# MainBoard.net
KiCad netlist of a schematic drawn in Altium Designer
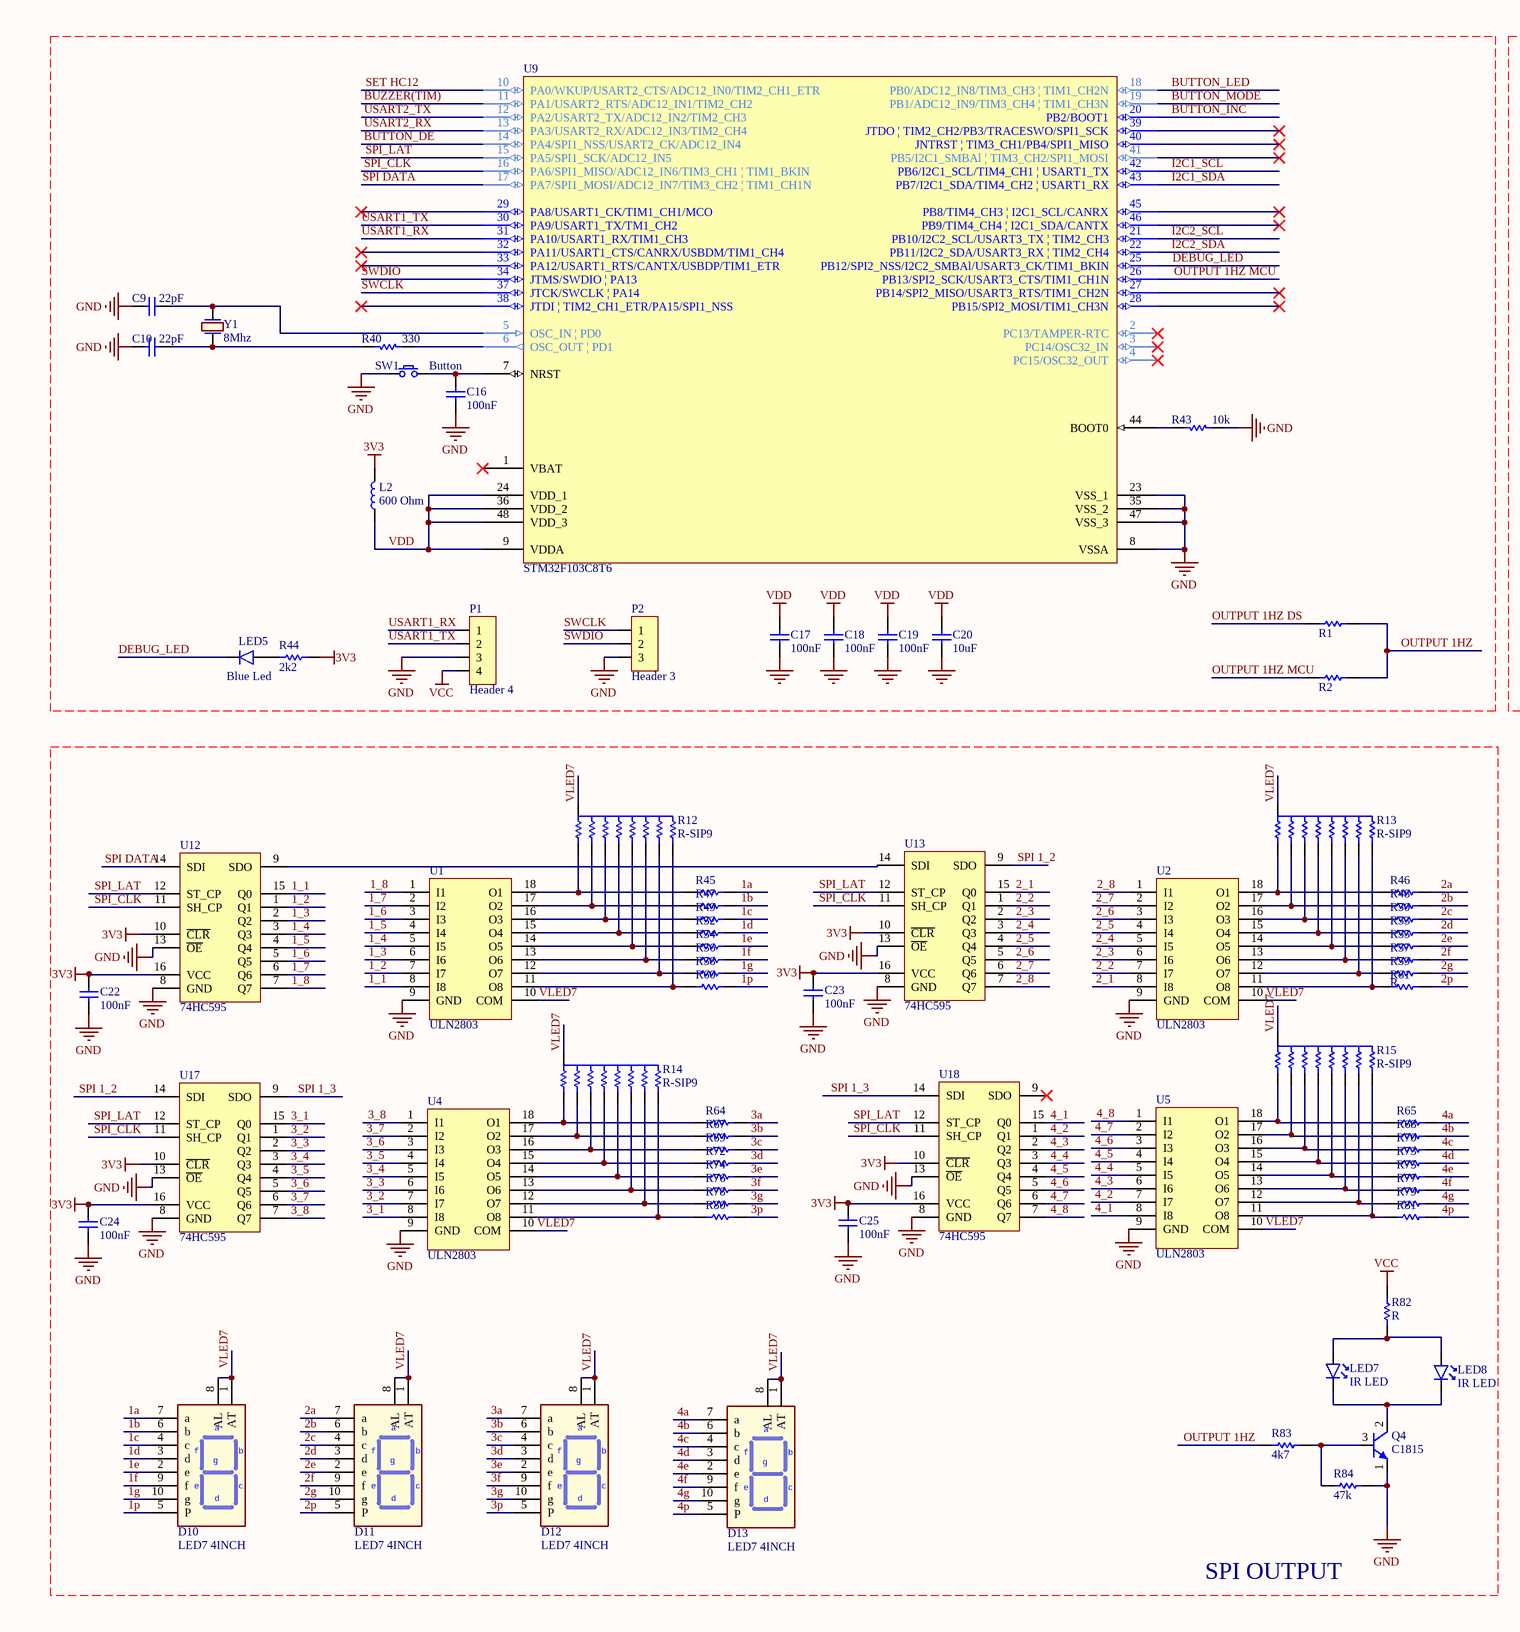
[diagram p0: MainBoard.SchDoc, left]
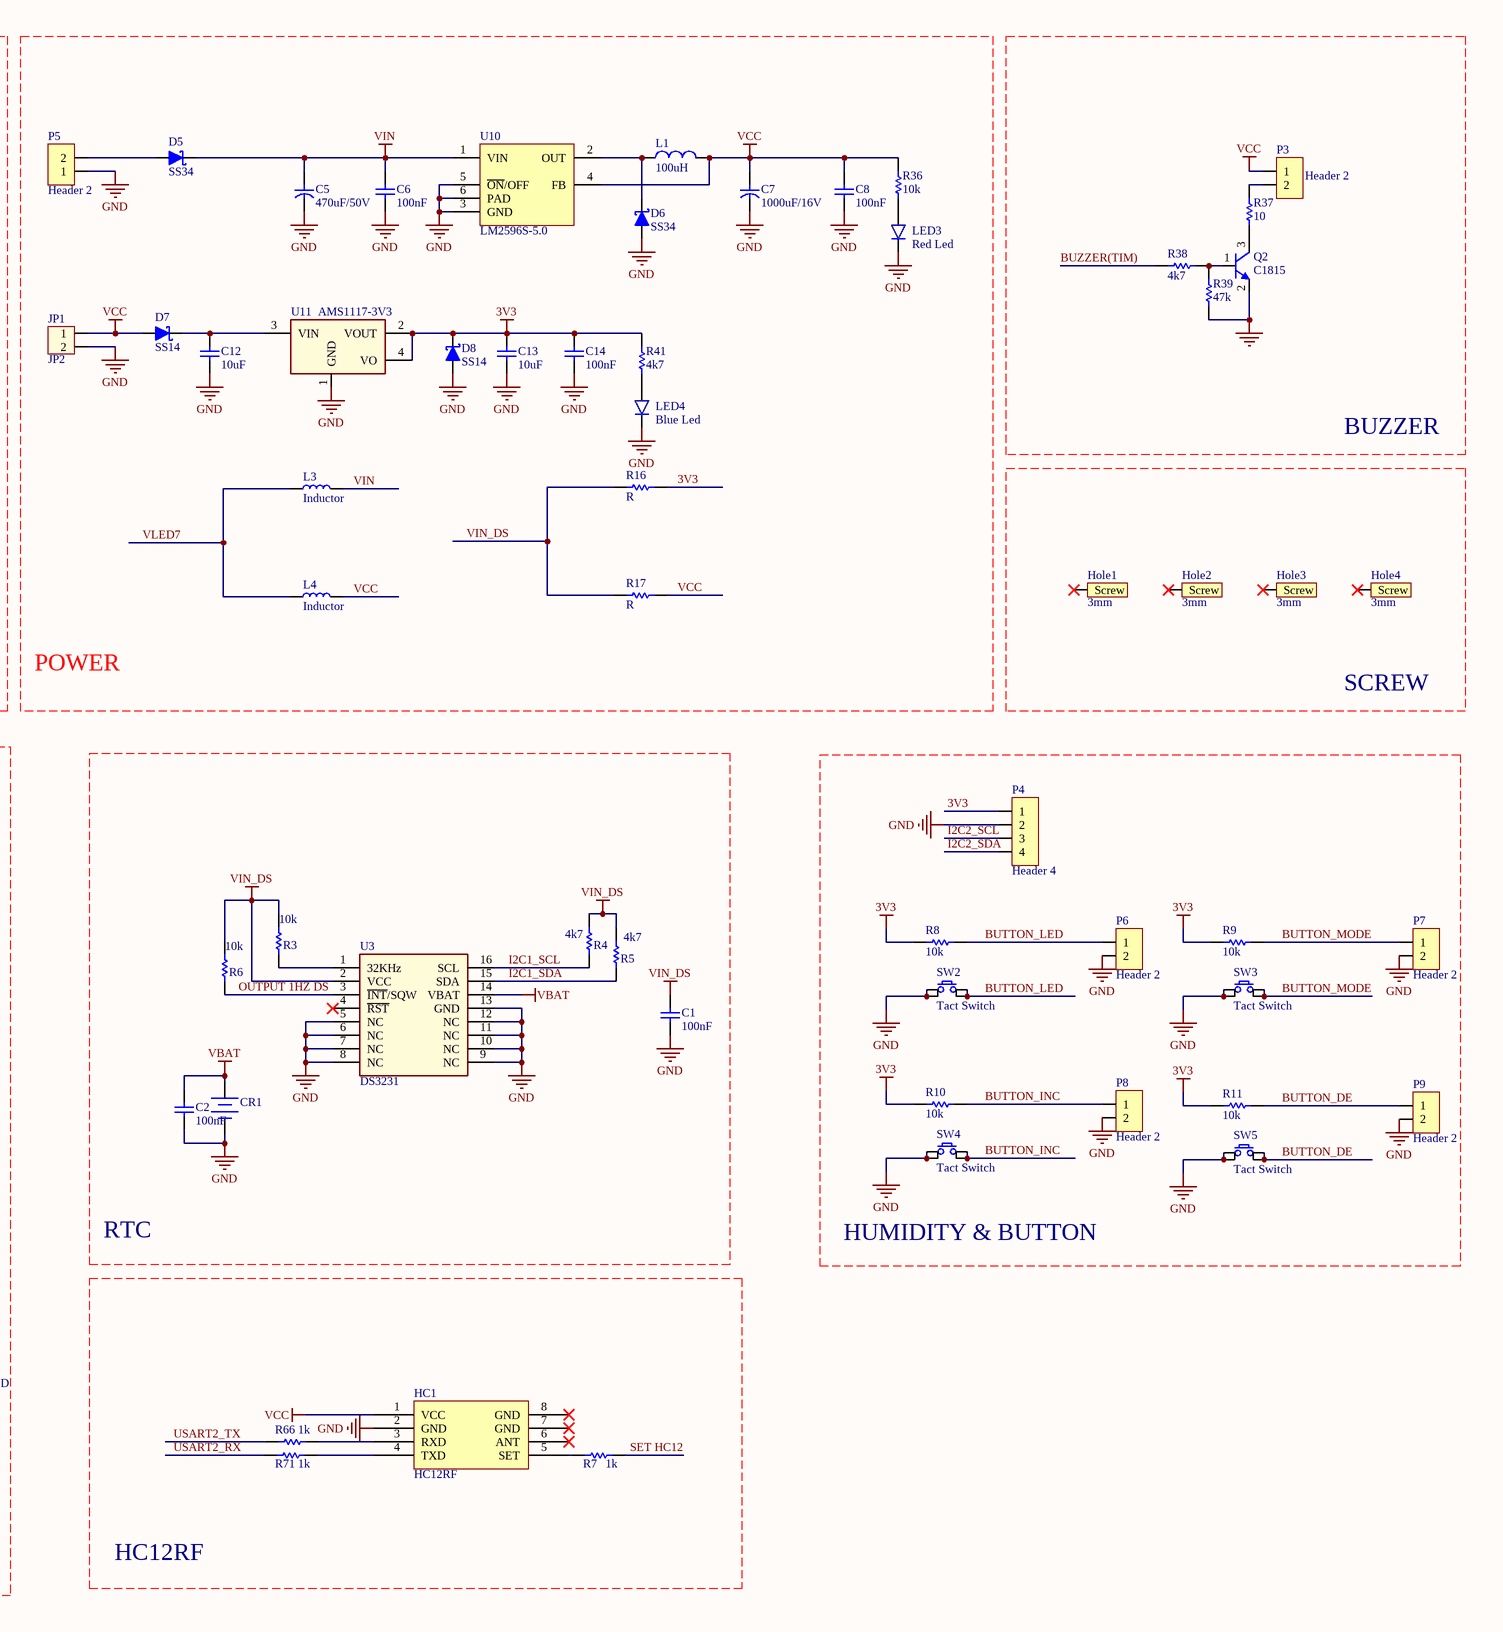
[diagram p1: MainBoard.SchDoc, right]

(export (version "E")
  (design (tool "Eeschema 10.0.6"))
  (components
    (comp (ref "C1")
      (value "100nF")
      (footprint "C 0805 (2012)")
      (description "Capacitor non-pol")
      (libsource (lib "BKIT4U_LIB") (part "Capacitor NP"))
    )
    (comp (ref "C2")
      (value "100nF")
      (footprint "C 0805 (2012)")
      (description "Capacitor non-pol")
      (libsource (lib "BKIT4U_LIB") (part "Capacitor NP"))
    )
    (comp (ref "C5")
      (value "470uF/50V")
      (footprint "CR/D.10.0x16.0/P.5.0")
      (description "Capacitor pol")
      (libsource (lib "BKIT4U_LIB") (part "Capacitor"))
    )
    (comp (ref "C6")
      (value "100nF")
      (footprint "C 0805 (2012)")
      (description "Capacitor non-pol")
      (libsource (lib "BKIT4U_LIB") (part "Capacitor NP"))
    )
    (comp (ref "C7")
      (value "1000uF/16V")
      (footprint "CR/D.10.0x12.5/P.5.0")
      (description "Capacitor pol")
      (libsource (lib "BKIT4U_LIB") (part "Capacitor"))
    )
    (comp (ref "C8")
      (value "100nF")
      (footprint "C 0805 (2012)")
      (description "Capacitor non-pol")
      (libsource (lib "BKIT4U_LIB") (part "Capacitor NP"))
    )
    (comp (ref "C9")
      (value "22pF")
      (footprint "C 0805 (2012)")
      (description "Capacitor non-pol")
      (libsource (lib "BKIT4U_LIB") (part "Capacitor NP"))
    )
    (comp (ref "C10")
      (value "22pF")
      (footprint "C 0805 (2012)")
      (description "Capacitor non-pol")
      (libsource (lib "BKIT4U_LIB") (part "Capacitor NP"))
    )
    (comp (ref "C12")
      (value "10uF")
      (footprint "C 0805 (2012)")
      (description "Capacitor non-pol")
      (libsource (lib "BKIT4U_LIB") (part "Capacitor NP"))
    )
    (comp (ref "C13")
      (value "10uF")
      (footprint "C 0805 (2012)")
      (description "Capacitor non-pol")
      (libsource (lib "BKIT4U_LIB") (part "Capacitor NP"))
    )
    (comp (ref "C14")
      (value "100nF")
      (footprint "C 0805 (2012)")
      (description "Capacitor non-pol")
      (libsource (lib "BKIT4U_LIB") (part "Capacitor NP"))
    )
    (comp (ref "C16")
      (value "100nF")
      (footprint "C 0805 (2012)")
      (description "Capacitor non-pol")
      (libsource (lib "BKIT4U_LIB") (part "Capacitor NP"))
    )
    (comp (ref "C17")
      (value "100nF")
      (footprint "C 0805 (2012)")
      (description "Capacitor non-pol")
      (libsource (lib "BKIT4U_LIB") (part "Capacitor NP"))
    )
    (comp (ref "C18")
      (value "100nF")
      (footprint "C 0805 (2012)")
      (description "Capacitor non-pol")
      (libsource (lib "BKIT4U_LIB") (part "Capacitor NP"))
    )
    (comp (ref "C19")
      (value "100nF")
      (footprint "C 0805 (2012)")
      (description "Capacitor non-pol")
      (libsource (lib "BKIT4U_LIB") (part "Capacitor NP"))
    )
    (comp (ref "C20")
      (value "10uF")
      (footprint "C 0805 (2012)")
      (description "Capacitor non-pol")
      (libsource (lib "BKIT4U_LIB") (part "Capacitor NP"))
    )
    (comp (ref "C22")
      (value "100nF")
      (footprint "C 0805 (2012)")
      (description "Capacitor non-pol")
      (libsource (lib "BKIT4U_LIB") (part "Capacitor NP"))
    )
    (comp (ref "C23")
      (value "100nF")
      (footprint "C 0805 (2012)")
      (description "Capacitor non-pol")
      (libsource (lib "BKIT4U_LIB") (part "Capacitor NP"))
    )
    (comp (ref "C24")
      (value "100nF")
      (footprint "C 0805 (2012)")
      (description "Capacitor non-pol")
      (libsource (lib "BKIT4U_LIB") (part "Capacitor NP"))
    )
    (comp (ref "C25")
      (value "100nF")
      (footprint "C 0805 (2012)")
      (description "Capacitor non-pol")
      (libsource (lib "BKIT4U_LIB") (part "Capacitor NP"))
    )
    (comp (ref "CR1") (value "~") (footprint "CON CR1220") (libsource (lib "BKIT4U_LIB") (part "Battery")))
    (comp (ref "D5")
      (value "SS34")
      (footprint "DO-214AC (SMA)")
      (description "Schottky Diode")
      (fields (field (name "PUBLISHER") "Altium Limited"))
      (libsource (lib "BKIT4U_LIB") (part "Diode Schottky"))
    )
    (comp (ref "D6")
      (value "SS34")
      (footprint "DO-214AC (SMA)")
      (description "Schottky Diode")
      (fields (field (name "PUBLISHER") "Altium Limited"))
      (libsource (lib "BKIT4U_LIB") (part "Diode Schottky"))
    )
    (comp (ref "D7")
      (value "SS14")
      (footprint "DO-214AC (SMA)")
      (description "Schottky Diode")
      (fields (field (name "PUBLISHER") "Altium Limited"))
      (libsource (lib "BKIT4U_LIB") (part "Diode Schottky"))
    )
    (comp (ref "D8")
      (value "SS14")
      (footprint "DO-214AC (SMA)")
      (description "Schottky Diode")
      (fields (field (name "PUBLISHER") "Altium Limited"))
      (libsource (lib "BKIT4U_LIB") (part "Diode Schottky"))
    )
    (comp (ref "D10")
      (value "LED7 4INCH")
      (footprint "LED7 CA 4INCH")
      (libsource (lib "BKIT4U_LIB") (part "LED7 4INCH"))
    )
    (comp (ref "D11")
      (value "LED7 4INCH")
      (footprint "LED7 CA 4INCH")
      (libsource (lib "BKIT4U_LIB") (part "LED7 4INCH"))
    )
    (comp (ref "D12")
      (value "LED7 4INCH")
      (footprint "LED7 CA 4INCH")
      (libsource (lib "BKIT4U_LIB") (part "LED7 4INCH"))
    )
    (comp (ref "D13")
      (value "LED7 4INCH")
      (footprint "LED7 CA 4INCH")
      (libsource (lib "BKIT4U_LIB") (part "LED7 4INCH"))
    )
    (comp (ref "HC1") (value "HC12RF") (footprint "HC12RF") (libsource (lib "BKIT4U_LIB") (part "HC12RF")))
    (comp (ref "Hole1") (value "3mm") (footprint "SCREW/3M/7M") (libsource (lib "BKIT4U_LIB") (part "Screw")))
    (comp (ref "Hole2") (value "3mm") (footprint "SCREW/3M/7M") (libsource (lib "BKIT4U_LIB") (part "Screw")))
    (comp (ref "Hole3") (value "3mm") (footprint "SCREW/3M/7M") (libsource (lib "BKIT4U_LIB") (part "Screw")))
    (comp (ref "Hole4") (value "3mm") (footprint "SCREW/3M/7M") (libsource (lib "BKIT4U_LIB") (part "Screw")))
    (comp (ref "JP1")
      (value "JP2")
      (footprint "CON Header 2")
      (description "Connector 2")
      (libsource (lib "BKIT4U_LIB") (part "Con2"))
    )
    (comp (ref "L1")
      (value "100uH")
      (footprint "Inductor SMD 12x12x8")
      (description "Inductor")
      (libsource (lib "syhaunguyen") (part "L1"))
    )
    (comp (ref "L2")
      (value "600 Ohm")
      (footprint "Inductor SMD 0805 (2012)")
      (description "Inductor")
      (libsource (lib "BKIT4U_LIB") (part "Inductor"))
    )
    (comp (ref "L3")
      (value "Inductor")
      (footprint "Inductor SMD 7.5x7.0x5.0")
      (libsource (lib "BKIT4U_LIB") (part "Inductor"))
    )
    (comp (ref "L4")
      (value "Inductor")
      (footprint "Inductor SMD 7.5x7.0x5.0")
      (libsource (lib "BKIT4U_LIB") (part "Inductor"))
    )
    (comp (ref "LED3")
      (value "Red Led")
      (footprint "Led SMD 0805")
      (description "Typical LED")
      (libsource (lib "BKIT4U_LIB") (part "Led"))
    )
    (comp (ref "LED4")
      (value "Blue Led")
      (footprint "Led SMD 0805")
      (description "Typical LED")
      (libsource (lib "BKIT4U_LIB") (part "Led"))
    )
    (comp (ref "LED5")
      (value "Blue Led")
      (footprint "Led SMD 0805")
      (description "Typical LED")
      (libsource (lib "BKIT4U_LIB") (part "Led"))
    )
    (comp (ref "LED7")
      (value "IR LED")
      (footprint "LED 5MM")
      (description "IR Led")
      (fields (field (name "PUBLISHER") "Altium Limited"))
      (libsource (lib "BKIT4U_LIB") (part "IR Led"))
    )
    (comp (ref "LED8")
      (value "IR LED")
      (footprint "LED 5MM")
      (description "IR Led")
      (fields (field (name "PUBLISHER") "Altium Limited"))
      (libsource (lib "BKIT4U_LIB") (part "IR Led"))
    )
    (comp (ref "P1")
      (value "Header 4")
      (footprint "CON Header 4")
      (description "Header, 4-Pin")
      (libsource (lib "BKIT4U_LIB") (part "Header 4"))
    )
    (comp (ref "P2")
      (value "Header 3")
      (footprint "Header 3")
      (description "Header, 3-Pin")
      (libsource (lib "BKIT4U_LIB") (part "Header 3"))
    )
    (comp (ref "P3")
      (value "Header 2")
      (footprint "CON Header 2")
      (description "Header, 2-Pin")
      (fields (field (name "PUBLISHER") "Altium Limited"))
      (libsource (lib "BKIT4U_LIB") (part "Header 2"))
    )
    (comp (ref "P4")
      (value "Header 4")
      (footprint "Header 4")
      (description "Header, 4-Pin")
      (libsource (lib "BKIT4U_LIB") (part "Header 4"))
    )
    (comp (ref "P5")
      (value "Header 2")
      (footprint "HDR Domino 2")
      (description "Header, 2-Pin")
      (fields (field (name "PUBLISHER") "Altium Limited"))
      (libsource (lib "") (part "Header 2_1"))
    )
    (comp (ref "P6")
      (value "Header 2")
      (footprint "CON Header 2")
      (description "Header, 2-Pin")
      (fields (field (name "PUBLISHER") "Altium Limited"))
      (libsource (lib "BKIT4U_LIB") (part "Header 2"))
    )
    (comp (ref "P7")
      (value "Header 2")
      (footprint "CON Header 2")
      (description "Header, 2-Pin")
      (fields (field (name "PUBLISHER") "Altium Limited"))
      (libsource (lib "BKIT4U_LIB") (part "Header 2"))
    )
    (comp (ref "P8")
      (value "Header 2")
      (footprint "CON Header 2")
      (description "Header, 2-Pin")
      (fields (field (name "PUBLISHER") "Altium Limited"))
      (libsource (lib "BKIT4U_LIB") (part "Header 2"))
    )
    (comp (ref "P9")
      (value "Header 2")
      (footprint "CON Header 2")
      (description "Header, 2-Pin")
      (fields (field (name "PUBLISHER") "Altium Limited"))
      (libsource (lib "BKIT4U_LIB") (part "Header 2"))
    )
    (comp (ref "Q2")
      (value "C1815")
      (footprint "SOT-23")
      (description "NPN Bipolar Transistor")
      (libsource (lib "BKIT4U_LIB") (part "Transistor NPN"))
    )
    (comp (ref "Q4")
      (value "C1815")
      (footprint "SOT-23")
      (description "NPN Bipolar Transistor")
      (libsource (lib "BKIT4U_LIB") (part "Transistor NPN - C1815"))
    )
    (comp (ref "R1")
      (value "R")
      (footprint "R 0805 (2012)")
      (description "Resistor")
      (fields (field (name "PUBLISHER") "Altium Limited"))
      (libsource (lib "BKIT4U_LIB") (part "Resistor"))
    )
    (comp (ref "R2")
      (value "R")
      (footprint "R 0805 (2012)")
      (description "Resistor")
      (fields (field (name "PUBLISHER") "Altium Limited"))
      (libsource (lib "BKIT4U_LIB") (part "Resistor"))
    )
    (comp (ref "R3")
      (value "10k")
      (footprint "R 0805 (2012)")
      (description "Resistor")
      (fields (field (name "PUBLISHER") "Altium Limited"))
      (libsource (lib "BKIT4U_LIB") (part "Resistor"))
    )
    (comp (ref "R4")
      (value "4k7")
      (footprint "R 0805 (2012)")
      (description "Resistor")
      (fields (field (name "PUBLISHER") "Altium Limited"))
      (libsource (lib "BKIT4U_LIB") (part "Resistor"))
    )
    (comp (ref "R5")
      (value "4k7")
      (footprint "R 0805 (2012)")
      (description "Resistor")
      (fields (field (name "PUBLISHER") "Altium Limited"))
      (libsource (lib "BKIT4U_LIB") (part "Resistor"))
    )
    (comp (ref "R6")
      (value "10k")
      (footprint "R 0805 (2012)")
      (description "Resistor")
      (fields (field (name "PUBLISHER") "Altium Limited"))
      (libsource (lib "BKIT4U_LIB") (part "Resistor"))
    )
    (comp (ref "R7")
      (value "1k")
      (footprint "R 0805 (2012)")
      (description "Resistor")
      (fields (field (name "PUBLISHER") "Altium Limited"))
      (libsource (lib "BKIT4U_LIB") (part "Resistor"))
    )
    (comp (ref "R8")
      (value "10k")
      (footprint "R 0805 (2012)")
      (description "Resistor")
      (fields (field (name "PUBLISHER") "Altium Limited"))
      (libsource (lib "BKIT4U_LIB") (part "Resistor"))
    )
    (comp (ref "R9")
      (value "10k")
      (footprint "R 0805 (2012)")
      (description "Resistor")
      (fields (field (name "PUBLISHER") "Altium Limited"))
      (libsource (lib "BKIT4U_LIB") (part "Resistor"))
    )
    (comp (ref "R10")
      (value "10k")
      (footprint "R 0805 (2012)")
      (description "Resistor")
      (fields (field (name "PUBLISHER") "Altium Limited"))
      (libsource (lib "BKIT4U_LIB") (part "Resistor"))
    )
    (comp (ref "R11")
      (value "10k")
      (footprint "R 0805 (2012)")
      (description "Resistor")
      (fields (field (name "PUBLISHER") "Altium Limited"))
      (libsource (lib "BKIT4U_LIB") (part "Resistor"))
    )
    (comp (ref "R12")
      (value "R-SIP9")
      (footprint "R SIP9")
      (description "Resistor")
      (fields (field (name "PUBLISHER") "Altium Limited"))
      (libsource (lib "BKIT4U_LIB") (part "Resistor Sip9"))
    )
    (comp (ref "R13")
      (value "R-SIP9")
      (footprint "R SIP9")
      (description "Resistor")
      (fields (field (name "PUBLISHER") "Altium Limited"))
      (libsource (lib "BKIT4U_LIB") (part "Resistor Sip9"))
    )
    (comp (ref "R14")
      (value "R-SIP9")
      (footprint "R SIP9")
      (description "Resistor")
      (fields (field (name "PUBLISHER") "Altium Limited"))
      (libsource (lib "BKIT4U_LIB") (part "Resistor Sip9"))
    )
    (comp (ref "R15")
      (value "R-SIP9")
      (footprint "R SIP9")
      (description "Resistor")
      (fields (field (name "PUBLISHER") "Altium Limited"))
      (libsource (lib "BKIT4U_LIB") (part "Resistor Sip9"))
    )
    (comp (ref "R16")
      (value "R")
      (footprint "R 0805 (2012)")
      (description "Resistor")
      (fields (field (name "PUBLISHER") "Altium Limited"))
      (libsource (lib "BKIT4U_LIB") (part "Resistor"))
    )
    (comp (ref "R17")
      (value "R")
      (footprint "R 0805 (2012)")
      (description "Resistor")
      (fields (field (name "PUBLISHER") "Altium Limited"))
      (libsource (lib "BKIT4U_LIB") (part "Resistor"))
    )
    (comp (ref "R36")
      (value "10k")
      (footprint "R 0805 (2012)")
      (description "Resistor")
      (fields (field (name "PUBLISHER") "Altium Limited"))
      (libsource (lib "BKIT4U_LIB") (part "Resistor"))
    )
    (comp (ref "R37")
      (value "10")
      (footprint "R 0805 (2012)")
      (description "Resistor")
      (fields (field (name "PUBLISHER") "Altium Limited"))
      (libsource (lib "BKIT4U_LIB") (part "Resistor"))
    )
    (comp (ref "R38")
      (value "4k7")
      (footprint "R 0805 (2012)")
      (description "Resistor")
      (fields (field (name "PUBLISHER") "Altium Limited"))
      (libsource (lib "BKIT4U_LIB") (part "Resistor"))
    )
    (comp (ref "R39")
      (value "47k")
      (footprint "R 0805 (2012)")
      (description "Resistor")
      (fields (field (name "PUBLISHER") "Altium Limited"))
      (libsource (lib "BKIT4U_LIB") (part "Resistor"))
    )
    (comp (ref "R40")
      (value "330")
      (footprint "R 0805 (2012)")
      (description "Resistor")
      (fields (field (name "PUBLISHER") "Altium Limited"))
      (libsource (lib "BKIT4U_LIB") (part "Resistor"))
    )
    (comp (ref "R41")
      (value "4k7")
      (footprint "R 0805 (2012)")
      (description "Resistor")
      (fields (field (name "PUBLISHER") "Altium Limited"))
      (libsource (lib "BKIT4U_LIB") (part "Resistor"))
    )
    (comp (ref "R43")
      (value "10k")
      (footprint "R 0805 (2012)")
      (description "Resistor")
      (fields (field (name "PUBLISHER") "Altium Limited"))
      (libsource (lib "BKIT4U_LIB") (part "Resistor"))
    )
    (comp (ref "R44")
      (value "2k2")
      (footprint "R 0805 (2012)")
      (description "Resistor")
      (fields (field (name "PUBLISHER") "Altium Limited"))
      (libsource (lib "BKIT4U_LIB") (part "Resistor"))
    )
    (comp (ref "R45")
      (value "R")
      (footprint "R 0805 (2012)")
      (description "Resistor")
      (fields (field (name "PUBLISHER") "Altium Limited"))
      (libsource (lib "BKIT4U_LIB") (part "Resistor"))
    )
    (comp (ref "R46")
      (value "R")
      (footprint "R 0805 (2012)")
      (description "Resistor")
      (fields (field (name "PUBLISHER") "Altium Limited"))
      (libsource (lib "BKIT4U_LIB") (part "Resistor"))
    )
    (comp (ref "R47")
      (value "R")
      (footprint "R 0805 (2012)")
      (description "Resistor")
      (fields (field (name "PUBLISHER") "Altium Limited"))
      (libsource (lib "BKIT4U_LIB") (part "Resistor"))
    )
    (comp (ref "R48")
      (value "R")
      (footprint "R 0805 (2012)")
      (description "Resistor")
      (fields (field (name "PUBLISHER") "Altium Limited"))
      (libsource (lib "BKIT4U_LIB") (part "Resistor"))
    )
    (comp (ref "R49")
      (value "R")
      (footprint "R 0805 (2012)")
      (description "Resistor")
      (fields (field (name "PUBLISHER") "Altium Limited"))
      (libsource (lib "BKIT4U_LIB") (part "Resistor"))
    )
    (comp (ref "R50")
      (value "R")
      (footprint "R 0805 (2012)")
      (description "Resistor")
      (fields (field (name "PUBLISHER") "Altium Limited"))
      (libsource (lib "BKIT4U_LIB") (part "Resistor"))
    )
    (comp (ref "R52")
      (value "R")
      (footprint "R 0805 (2012)")
      (description "Resistor")
      (fields (field (name "PUBLISHER") "Altium Limited"))
      (libsource (lib "BKIT4U_LIB") (part "Resistor"))
    )
    (comp (ref "R53")
      (value "R")
      (footprint "R 0805 (2012)")
      (description "Resistor")
      (fields (field (name "PUBLISHER") "Altium Limited"))
      (libsource (lib "BKIT4U_LIB") (part "Resistor"))
    )
    (comp (ref "R54")
      (value "R")
      (footprint "R 0805 (2012)")
      (description "Resistor")
      (fields (field (name "PUBLISHER") "Altium Limited"))
      (libsource (lib "BKIT4U_LIB") (part "Resistor"))
    )
    (comp (ref "R55")
      (value "R")
      (footprint "R 0805 (2012)")
      (description "Resistor")
      (fields (field (name "PUBLISHER") "Altium Limited"))
      (libsource (lib "BKIT4U_LIB") (part "Resistor"))
    )
    (comp (ref "R56")
      (value "R")
      (footprint "R 0805 (2012)")
      (description "Resistor")
      (fields (field (name "PUBLISHER") "Altium Limited"))
      (libsource (lib "BKIT4U_LIB") (part "Resistor"))
    )
    (comp (ref "R57")
      (value "R")
      (footprint "R 0805 (2012)")
      (description "Resistor")
      (fields (field (name "PUBLISHER") "Altium Limited"))
      (libsource (lib "BKIT4U_LIB") (part "Resistor"))
    )
    (comp (ref "R58")
      (value "R")
      (footprint "R 0805 (2012)")
      (description "Resistor")
      (fields (field (name "PUBLISHER") "Altium Limited"))
      (libsource (lib "BKIT4U_LIB") (part "Resistor"))
    )
    (comp (ref "R59")
      (value "R")
      (footprint "R 0805 (2012)")
      (description "Resistor")
      (fields (field (name "PUBLISHER") "Altium Limited"))
      (libsource (lib "BKIT4U_LIB") (part "Resistor"))
    )
    (comp (ref "R60")
      (value "R")
      (footprint "R 0805 (2012)")
      (description "Resistor")
      (fields (field (name "PUBLISHER") "Altium Limited"))
      (libsource (lib "BKIT4U_LIB") (part "Resistor"))
    )
    (comp (ref "R61")
      (value "R")
      (footprint "R 0805 (2012)")
      (description "Resistor")
      (fields (field (name "PUBLISHER") "Altium Limited"))
      (libsource (lib "BKIT4U_LIB") (part "Resistor"))
    )
    (comp (ref "R64")
      (value "R")
      (footprint "R 0805 (2012)")
      (description "Resistor")
      (fields (field (name "PUBLISHER") "Altium Limited"))
      (libsource (lib "BKIT4U_LIB") (part "Resistor"))
    )
    (comp (ref "R65")
      (value "R")
      (footprint "R 0805 (2012)")
      (description "Resistor")
      (fields (field (name "PUBLISHER") "Altium Limited"))
      (libsource (lib "BKIT4U_LIB") (part "Resistor"))
    )
    (comp (ref "R66")
      (value "1k")
      (footprint "R 0805 (2012)")
      (description "Resistor")
      (fields (field (name "PUBLISHER") "Altium Limited"))
      (libsource (lib "BKIT4U_LIB") (part "Resistor"))
    )
    (comp (ref "R67")
      (value "R")
      (footprint "R 0805 (2012)")
      (description "Resistor")
      (fields (field (name "PUBLISHER") "Altium Limited"))
      (libsource (lib "BKIT4U_LIB") (part "Resistor"))
    )
    (comp (ref "R68")
      (value "R")
      (footprint "R 0805 (2012)")
      (description "Resistor")
      (fields (field (name "PUBLISHER") "Altium Limited"))
      (libsource (lib "BKIT4U_LIB") (part "Resistor"))
    )
    (comp (ref "R69")
      (value "R")
      (footprint "R 0805 (2012)")
      (description "Resistor")
      (fields (field (name "PUBLISHER") "Altium Limited"))
      (libsource (lib "BKIT4U_LIB") (part "Resistor"))
    )
    (comp (ref "R70")
      (value "R")
      (footprint "R 0805 (2012)")
      (description "Resistor")
      (fields (field (name "PUBLISHER") "Altium Limited"))
      (libsource (lib "BKIT4U_LIB") (part "Resistor"))
    )
    (comp (ref "R71")
      (value "1k")
      (footprint "R 0805 (2012)")
      (description "Resistor")
      (fields (field (name "PUBLISHER") "Altium Limited"))
      (libsource (lib "BKIT4U_LIB") (part "Resistor"))
    )
    (comp (ref "R72")
      (value "R")
      (footprint "R 0805 (2012)")
      (description "Resistor")
      (fields (field (name "PUBLISHER") "Altium Limited"))
      (libsource (lib "BKIT4U_LIB") (part "Resistor"))
    )
    (comp (ref "R73")
      (value "R")
      (footprint "R 0805 (2012)")
      (description "Resistor")
      (fields (field (name "PUBLISHER") "Altium Limited"))
      (libsource (lib "BKIT4U_LIB") (part "Resistor"))
    )
    (comp (ref "R74")
      (value "R")
      (footprint "R 0805 (2012)")
      (description "Resistor")
      (fields (field (name "PUBLISHER") "Altium Limited"))
      (libsource (lib "BKIT4U_LIB") (part "Resistor"))
    )
    (comp (ref "R75")
      (value "R")
      (footprint "R 0805 (2012)")
      (description "Resistor")
      (fields (field (name "PUBLISHER") "Altium Limited"))
      (libsource (lib "BKIT4U_LIB") (part "Resistor"))
    )
    (comp (ref "R76")
      (value "R")
      (footprint "R 0805 (2012)")
      (description "Resistor")
      (fields (field (name "PUBLISHER") "Altium Limited"))
      (libsource (lib "BKIT4U_LIB") (part "Resistor"))
    )
    (comp (ref "R77")
      (value "R")
      (footprint "R 0805 (2012)")
      (description "Resistor")
      (fields (field (name "PUBLISHER") "Altium Limited"))
      (libsource (lib "BKIT4U_LIB") (part "Resistor"))
    )
    (comp (ref "R78")
      (value "R")
      (footprint "R 0805 (2012)")
      (description "Resistor")
      (fields (field (name "PUBLISHER") "Altium Limited"))
      (libsource (lib "BKIT4U_LIB") (part "Resistor"))
    )
    (comp (ref "R79")
      (value "R")
      (footprint "R 0805 (2012)")
      (description "Resistor")
      (fields (field (name "PUBLISHER") "Altium Limited"))
      (libsource (lib "BKIT4U_LIB") (part "Resistor"))
    )
    (comp (ref "R80")
      (value "R")
      (footprint "R 0805 (2012)")
      (description "Resistor")
      (fields (field (name "PUBLISHER") "Altium Limited"))
      (libsource (lib "BKIT4U_LIB") (part "Resistor"))
    )
    (comp (ref "R81")
      (value "R")
      (footprint "R 0805 (2012)")
      (description "Resistor")
      (fields (field (name "PUBLISHER") "Altium Limited"))
      (libsource (lib "BKIT4U_LIB") (part "Resistor"))
    )
    (comp (ref "R82")
      (value "R")
      (footprint "R 0805 (2012)")
      (description "Resistor")
      (fields (field (name "PUBLISHER") "Altium Limited"))
      (libsource (lib "BKIT4U_LIB") (part "Resistor"))
    )
    (comp (ref "R83")
      (value "4k7")
      (footprint "R 0805 (2012)")
      (description "Resistor")
      (fields (field (name "PUBLISHER") "Altium Limited"))
      (libsource (lib "BKIT4U_LIB") (part "Resistor"))
    )
    (comp (ref "R84")
      (value "47k")
      (footprint "R 0805 (2012)")
      (description "Resistor")
      (fields (field (name "PUBLISHER") "Altium Limited"))
      (libsource (lib "BKIT4U_LIB") (part "Resistor"))
    )
    (comp (ref "SW1")
      (value "Button")
      (footprint "SW/2/SMD")
      (description "Tact switch 2 pin")
      (libsource (lib "BKIT4U_LIB") (part "SW SPST"))
    )
    (comp (ref "SW2")
      (value "Tact Switch")
      (footprint "SW/4/SMD/SMALL")
      (description "Tact switch 4 pin")
      (libsource (lib "BKIT4U_LIB") (part "SW SPST-4"))
    )
    (comp (ref "SW3")
      (value "Tact Switch")
      (footprint "SW/4/SMD/SMALL")
      (description "Tact switch 4 pin")
      (libsource (lib "BKIT4U_LIB") (part "SW SPST-4"))
    )
    (comp (ref "SW4")
      (value "Tact Switch")
      (footprint "SW/4/SMD/SMALL")
      (description "Tact switch 4 pin")
      (libsource (lib "BKIT4U_LIB") (part "SW SPST-4"))
    )
    (comp (ref "SW5")
      (value "Tact Switch")
      (footprint "SW/4/SMD/SMALL")
      (description "Tact switch 4 pin")
      (libsource (lib "BKIT4U_LIB") (part "SW SPST-4"))
    )
    (comp (ref "U1")
      (value "ULN2803")
      (footprint "SOIC-18")
      (description "High-voltage, high-current Darlington transistor arrays")
      (libsource (lib "BKIT4U_LIB") (part "ULN2803"))
    )
    (comp (ref "U2")
      (value "ULN2803")
      (footprint "SOIC-18")
      (description "High-voltage, high-current Darlington transistor arrays")
      (libsource (lib "BKIT4U_LIB") (part "ULN2803"))
    )
    (comp (ref "U3")
      (value "DS3231")
      (footprint "SOIC-16-WIDE")
      (libsource (lib "BKIT4U_LIB") (part "DS3231"))
    )
    (comp (ref "U4")
      (value "ULN2803")
      (footprint "SOIC-18")
      (description "High-voltage, high-current Darlington transistor arrays")
      (libsource (lib "BKIT4U_LIB") (part "ULN2803"))
    )
    (comp (ref "U5")
      (value "ULN2803")
      (footprint "SOIC-18")
      (description "High-voltage, high-current Darlington transistor arrays")
      (libsource (lib "BKIT4U_LIB") (part "ULN2803"))
    )
    (comp (ref "U9")
      (value "STM32F103C8T6")
      (footprint "LQFP48_N")
      (description "STM32 ARM-based 32-bit MCU with 64 Kbytes Flash, 48-pin LQFP, Industrial Temperature")
      (fields (field (name "PUBLISHER") "Altium Limited"))
      (libsource (lib "BKIT4U_LIB") (part "STM32F103C8T6"))
    )
    (comp (ref "U10")
      (value "LM2596S-5.0")
      (footprint "TO-263-5")
      (description "SIMPLE SWITCHER® 3A Step-Down Voltage Regulator")
      (libsource (lib "BKIT4U_LIB") (part "LM2576/96"))
    )
    (comp (ref "U11")
      (value "AMS1117-3V3")
      (footprint "SOT-223")
      (description "1A LDO Voltage Regulator, ADJ or fixed 1.5/1.8/2.5/2.85/3.3/5V")
      (libsource (lib "BKIT4U_LIB") (part "AMS1117"))
    )
    (comp (ref "U12")
      (value "74HC595")
      (footprint "SOIC-16")
      (description "8-bit serial-in, serial or parallel-out  shift register with output latches;  3-state")
      (libsource (lib "BKIT4U_LIB") (part "74HC595"))
    )
    (comp (ref "U13")
      (value "74HC595")
      (footprint "SOIC-16")
      (description "8-bit serial-in, serial or parallel-out  shift register with output latches;  3-state")
      (libsource (lib "BKIT4U_LIB") (part "74HC595"))
    )
    (comp (ref "U17")
      (value "74HC595")
      (footprint "SOIC-16")
      (description "8-bit serial-in, serial or parallel-out  shift register with output latches;  3-state")
      (libsource (lib "BKIT4U_LIB") (part "74HC595"))
    )
    (comp (ref "U18")
      (value "74HC595")
      (footprint "SOIC-16")
      (description "8-bit serial-in, serial or parallel-out  shift register with output latches;  3-state")
      (libsource (lib "BKIT4U_LIB") (part "74HC595"))
    )
    (comp (ref "Y1")
      (value "8Mhz")
      (footprint "Crystal HC49US SMD")
      (libsource (lib "BKIT4U_LIB") (part "Crystal"))
    )
  )
  (nets
    (net (code "1") (name "/1_1") (class "Default")
      (node (ref "U1") (pin "8") (pinfunction "I8_8") (pintype "passive"))
      (node (ref "U12") (pin "15") (pinfunction "Q0_15") (pintype "passive"))
    )
    (net (code "2") (name "/1_2") (class "Default")
      (node (ref "U1") (pin "7") (pinfunction "I7_7") (pintype "passive"))
      (node (ref "U12") (pin "1") (pinfunction "Q1_1") (pintype "passive"))
    )
    (net (code "3") (name "/1_3") (class "Default")
      (node (ref "U1") (pin "6") (pinfunction "I6_6") (pintype "passive"))
      (node (ref "U12") (pin "2") (pinfunction "Q2_2") (pintype "passive"))
    )
    (net (code "4") (name "/1_4") (class "Default")
      (node (ref "U1") (pin "5") (pinfunction "I5_5") (pintype "passive"))
      (node (ref "U12") (pin "3") (pinfunction "Q3_3") (pintype "passive"))
    )
    (net (code "5") (name "/1_5") (class "Default")
      (node (ref "U1") (pin "4") (pinfunction "I4_4") (pintype "passive"))
      (node (ref "U12") (pin "4") (pinfunction "Q4_4") (pintype "passive"))
    )
    (net (code "6") (name "/1_6") (class "Default")
      (node (ref "U1") (pin "3") (pinfunction "I3_3") (pintype "passive"))
      (node (ref "U12") (pin "5") (pinfunction "Q5_5") (pintype "passive"))
    )
    (net (code "7") (name "/1_7") (class "Default")
      (node (ref "U1") (pin "2") (pinfunction "I2_2") (pintype "passive"))
      (node (ref "U12") (pin "6") (pinfunction "Q6_6") (pintype "passive"))
    )
    (net (code "8") (name "/1_8") (class "Default")
      (node (ref "U1") (pin "1") (pinfunction "I1_1") (pintype "passive"))
      (node (ref "U12") (pin "7") (pinfunction "Q7_7") (pintype "passive"))
    )
    (net (code "9") (name "/1a") (class "Default")
      (node (ref "D10") (pin "7") (pinfunction "a_7") (pintype "passive"))
      (node (ref "R45") (pin "2") (pinfunction "2_2") (pintype "passive"))
    )
    (net (code "10") (name "/1b") (class "Default")
      (node (ref "D10") (pin "6") (pinfunction "b_6") (pintype "passive"))
      (node (ref "R47") (pin "2") (pinfunction "2_2") (pintype "passive"))
    )
    (net (code "11") (name "/1c") (class "Default")
      (node (ref "D10") (pin "4") (pinfunction "c_4") (pintype "passive"))
      (node (ref "R49") (pin "2") (pinfunction "2_2") (pintype "passive"))
    )
    (net (code "12") (name "/1d") (class "Default")
      (node (ref "D10") (pin "3") (pinfunction "d_3") (pintype "passive"))
      (node (ref "R52") (pin "2") (pinfunction "2_2") (pintype "passive"))
    )
    (net (code "13") (name "/1e") (class "Default")
      (node (ref "D10") (pin "2") (pinfunction "e_2") (pintype "passive"))
      (node (ref "R54") (pin "2") (pinfunction "2_2") (pintype "passive"))
    )
    (net (code "14") (name "/1f") (class "Default")
      (node (ref "D10") (pin "9") (pinfunction "f_9") (pintype "passive"))
      (node (ref "R56") (pin "2") (pinfunction "2_2") (pintype "passive"))
    )
    (net (code "15") (name "/1g") (class "Default")
      (node (ref "D10") (pin "10") (pinfunction "g_10") (pintype "passive"))
      (node (ref "R58") (pin "2") (pinfunction "2_2") (pintype "passive"))
    )
    (net (code "16") (name "/1p") (class "Default")
      (node (ref "D10") (pin "5") (pinfunction "P_5") (pintype "passive"))
      (node (ref "R60") (pin "2") (pinfunction "2_2") (pintype "passive"))
    )
    (net (code "17") (name "/2_1") (class "Default")
      (node (ref "U13") (pin "15") (pinfunction "Q0_15") (pintype "passive"))
      (node (ref "U2") (pin "8") (pinfunction "I8_8") (pintype "passive"))
    )
    (net (code "18") (name "/2_2") (class "Default")
      (node (ref "U13") (pin "1") (pinfunction "Q1_1") (pintype "passive"))
      (node (ref "U2") (pin "7") (pinfunction "I7_7") (pintype "passive"))
    )
    (net (code "19") (name "/2_3") (class "Default")
      (node (ref "U13") (pin "2") (pinfunction "Q2_2") (pintype "passive"))
      (node (ref "U2") (pin "6") (pinfunction "I6_6") (pintype "passive"))
    )
    (net (code "20") (name "/2_4") (class "Default")
      (node (ref "U13") (pin "3") (pinfunction "Q3_3") (pintype "passive"))
      (node (ref "U2") (pin "5") (pinfunction "I5_5") (pintype "passive"))
    )
    (net (code "21") (name "/2_5") (class "Default")
      (node (ref "U13") (pin "4") (pinfunction "Q4_4") (pintype "passive"))
      (node (ref "U2") (pin "4") (pinfunction "I4_4") (pintype "passive"))
    )
    (net (code "22") (name "/2_6") (class "Default")
      (node (ref "U13") (pin "5") (pinfunction "Q5_5") (pintype "passive"))
      (node (ref "U2") (pin "3") (pinfunction "I3_3") (pintype "passive"))
    )
    (net (code "23") (name "/2_7") (class "Default")
      (node (ref "U13") (pin "6") (pinfunction "Q6_6") (pintype "passive"))
      (node (ref "U2") (pin "2") (pinfunction "I2_2") (pintype "passive"))
    )
    (net (code "24") (name "/2_8") (class "Default")
      (node (ref "U13") (pin "7") (pinfunction "Q7_7") (pintype "passive"))
      (node (ref "U2") (pin "1") (pinfunction "I1_1") (pintype "passive"))
    )
    (net (code "25") (name "/2a") (class "Default")
      (node (ref "D11") (pin "7") (pinfunction "a_7") (pintype "passive"))
      (node (ref "R46") (pin "2") (pinfunction "2_2") (pintype "passive"))
    )
    (net (code "26") (name "/2b") (class "Default")
      (node (ref "D11") (pin "6") (pinfunction "b_6") (pintype "passive"))
      (node (ref "R48") (pin "2") (pinfunction "2_2") (pintype "passive"))
    )
    (net (code "27") (name "/2c") (class "Default")
      (node (ref "D11") (pin "4") (pinfunction "c_4") (pintype "passive"))
      (node (ref "R50") (pin "2") (pinfunction "2_2") (pintype "passive"))
    )
    (net (code "28") (name "/2d") (class "Default")
      (node (ref "D11") (pin "3") (pinfunction "d_3") (pintype "passive"))
      (node (ref "R53") (pin "2") (pinfunction "2_2") (pintype "passive"))
    )
    (net (code "29") (name "/2e") (class "Default")
      (node (ref "D11") (pin "2") (pinfunction "e_2") (pintype "passive"))
      (node (ref "R55") (pin "2") (pinfunction "2_2") (pintype "passive"))
    )
    (net (code "30") (name "/2f") (class "Default")
      (node (ref "D11") (pin "9") (pinfunction "f_9") (pintype "passive"))
      (node (ref "R57") (pin "2") (pinfunction "2_2") (pintype "passive"))
    )
    (net (code "31") (name "/2g") (class "Default")
      (node (ref "D11") (pin "10") (pinfunction "g_10") (pintype "passive"))
      (node (ref "R59") (pin "2") (pinfunction "2_2") (pintype "passive"))
    )
    (net (code "32") (name "/2p") (class "Default")
      (node (ref "D11") (pin "5") (pinfunction "P_5") (pintype "passive"))
      (node (ref "R61") (pin "2") (pinfunction "2_2") (pintype "passive"))
    )
    (net (code "33") (name "/3_1") (class "Default")
      (node (ref "U17") (pin "15") (pinfunction "Q0_15") (pintype "passive"))
      (node (ref "U4") (pin "8") (pinfunction "I8_8") (pintype "passive"))
    )
    (net (code "34") (name "/3_2") (class "Default")
      (node (ref "U17") (pin "1") (pinfunction "Q1_1") (pintype "passive"))
      (node (ref "U4") (pin "7") (pinfunction "I7_7") (pintype "passive"))
    )
    (net (code "35") (name "/3_3") (class "Default")
      (node (ref "U17") (pin "2") (pinfunction "Q2_2") (pintype "passive"))
      (node (ref "U4") (pin "6") (pinfunction "I6_6") (pintype "passive"))
    )
    (net (code "36") (name "/3_4") (class "Default")
      (node (ref "U17") (pin "3") (pinfunction "Q3_3") (pintype "passive"))
      (node (ref "U4") (pin "5") (pinfunction "I5_5") (pintype "passive"))
    )
    (net (code "37") (name "/3_5") (class "Default")
      (node (ref "U17") (pin "4") (pinfunction "Q4_4") (pintype "passive"))
      (node (ref "U4") (pin "4") (pinfunction "I4_4") (pintype "passive"))
    )
    (net (code "38") (name "/3_6") (class "Default")
      (node (ref "U17") (pin "5") (pinfunction "Q5_5") (pintype "passive"))
      (node (ref "U4") (pin "3") (pinfunction "I3_3") (pintype "passive"))
    )
    (net (code "39") (name "/3_7") (class "Default")
      (node (ref "U17") (pin "6") (pinfunction "Q6_6") (pintype "passive"))
      (node (ref "U4") (pin "2") (pinfunction "I2_2") (pintype "passive"))
    )
    (net (code "40") (name "/3_8") (class "Default")
      (node (ref "U17") (pin "7") (pinfunction "Q7_7") (pintype "passive"))
      (node (ref "U4") (pin "1") (pinfunction "I1_1") (pintype "passive"))
    )
    (net (code "41") (name "/3a") (class "Default")
      (node (ref "D12") (pin "7") (pinfunction "a_7") (pintype "passive"))
      (node (ref "R64") (pin "2") (pinfunction "2_2") (pintype "passive"))
    )
    (net (code "42") (name "/3b") (class "Default")
      (node (ref "D12") (pin "6") (pinfunction "b_6") (pintype "passive"))
      (node (ref "R67") (pin "2") (pinfunction "2_2") (pintype "passive"))
    )
    (net (code "43") (name "/3c") (class "Default")
      (node (ref "D12") (pin "4") (pinfunction "c_4") (pintype "passive"))
      (node (ref "R69") (pin "2") (pinfunction "2_2") (pintype "passive"))
    )
    (net (code "44") (name "/3d") (class "Default")
      (node (ref "D12") (pin "3") (pinfunction "d_3") (pintype "passive"))
      (node (ref "R72") (pin "2") (pinfunction "2_2") (pintype "passive"))
    )
    (net (code "45") (name "/3e") (class "Default")
      (node (ref "D12") (pin "2") (pinfunction "e_2") (pintype "passive"))
      (node (ref "R74") (pin "2") (pinfunction "2_2") (pintype "passive"))
    )
    (net (code "46") (name "/3f") (class "Default")
      (node (ref "D12") (pin "9") (pinfunction "f_9") (pintype "passive"))
      (node (ref "R76") (pin "2") (pinfunction "2_2") (pintype "passive"))
    )
    (net (code "47") (name "/3g") (class "Default")
      (node (ref "D12") (pin "10") (pinfunction "g_10") (pintype "passive"))
      (node (ref "R78") (pin "2") (pinfunction "2_2") (pintype "passive"))
    )
    (net (code "48") (name "/3p") (class "Default")
      (node (ref "D12") (pin "5") (pinfunction "P_5") (pintype "passive"))
      (node (ref "R80") (pin "2") (pinfunction "2_2") (pintype "passive"))
    )
    (net (code "49") (name "/4_1") (class "Default")
      (node (ref "U18") (pin "15") (pinfunction "Q0_15") (pintype "passive"))
      (node (ref "U5") (pin "8") (pinfunction "I8_8") (pintype "passive"))
    )
    (net (code "50") (name "/4_2") (class "Default")
      (node (ref "U18") (pin "1") (pinfunction "Q1_1") (pintype "passive"))
      (node (ref "U5") (pin "7") (pinfunction "I7_7") (pintype "passive"))
    )
    (net (code "51") (name "/4_3") (class "Default")
      (node (ref "U18") (pin "2") (pinfunction "Q2_2") (pintype "passive"))
      (node (ref "U5") (pin "6") (pinfunction "I6_6") (pintype "passive"))
    )
    (net (code "52") (name "/4_4") (class "Default")
      (node (ref "U18") (pin "3") (pinfunction "Q3_3") (pintype "passive"))
      (node (ref "U5") (pin "5") (pinfunction "I5_5") (pintype "passive"))
    )
    (net (code "53") (name "/4_5") (class "Default")
      (node (ref "U18") (pin "4") (pinfunction "Q4_4") (pintype "passive"))
      (node (ref "U5") (pin "4") (pinfunction "I4_4") (pintype "passive"))
    )
    (net (code "54") (name "/4_6") (class "Default")
      (node (ref "U18") (pin "5") (pinfunction "Q5_5") (pintype "passive"))
      (node (ref "U5") (pin "3") (pinfunction "I3_3") (pintype "passive"))
    )
    (net (code "55") (name "/4_7") (class "Default")
      (node (ref "U18") (pin "6") (pinfunction "Q6_6") (pintype "passive"))
      (node (ref "U5") (pin "2") (pinfunction "I2_2") (pintype "passive"))
    )
    (net (code "56") (name "/4_8") (class "Default")
      (node (ref "U18") (pin "7") (pinfunction "Q7_7") (pintype "passive"))
      (node (ref "U5") (pin "1") (pinfunction "I1_1") (pintype "passive"))
    )
    (net (code "57") (name "/4a") (class "Default")
      (node (ref "D13") (pin "7") (pinfunction "a_7") (pintype "passive"))
      (node (ref "R65") (pin "2") (pinfunction "2_2") (pintype "passive"))
    )
    (net (code "58") (name "/4b") (class "Default")
      (node (ref "D13") (pin "6") (pinfunction "b_6") (pintype "passive"))
      (node (ref "R68") (pin "2") (pinfunction "2_2") (pintype "passive"))
    )
    (net (code "59") (name "/4c") (class "Default")
      (node (ref "D13") (pin "4") (pinfunction "c_4") (pintype "passive"))
      (node (ref "R70") (pin "2") (pinfunction "2_2") (pintype "passive"))
    )
    (net (code "60") (name "/4d") (class "Default")
      (node (ref "D13") (pin "3") (pinfunction "d_3") (pintype "passive"))
      (node (ref "R73") (pin "2") (pinfunction "2_2") (pintype "passive"))
    )
    (net (code "61") (name "/4e") (class "Default")
      (node (ref "D13") (pin "2") (pinfunction "e_2") (pintype "passive"))
      (node (ref "R75") (pin "2") (pinfunction "2_2") (pintype "passive"))
    )
    (net (code "62") (name "/4f") (class "Default")
      (node (ref "D13") (pin "9") (pinfunction "f_9") (pintype "passive"))
      (node (ref "R77") (pin "2") (pinfunction "2_2") (pintype "passive"))
    )
    (net (code "63") (name "/4g") (class "Default")
      (node (ref "D13") (pin "10") (pinfunction "g_10") (pintype "passive"))
      (node (ref "R79") (pin "2") (pinfunction "2_2") (pintype "passive"))
    )
    (net (code "64") (name "/4p") (class "Default")
      (node (ref "D13") (pin "5") (pinfunction "P_5") (pintype "passive"))
      (node (ref "R81") (pin "2") (pinfunction "2_2") (pintype "passive"))
    )
    (net (code "65") (name "/BUTTON_DE") (class "Default")
      (node (ref "P9") (pin "1") (pinfunction "1_1") (pintype "passive"))
      (node (ref "R11") (pin "2") (pinfunction "2_2") (pintype "passive"))
      (node (ref "SW5") (pin "2") (pinfunction "2_2") (pintype "passive"))
      (node (ref "SW5") (pin "3") (pinfunction "1_3") (pintype "passive"))
      (node (ref "U9") (pin "14") (pinfunction "PA4/SPI1_NSS/USART2_CK/ADC12_IN4_14") (pintype "bidirectional"))
    )
    (net (code "66") (name "/BUTTON_INC") (class "Default")
      (node (ref "P8") (pin "1") (pinfunction "1_1") (pintype "passive"))
      (node (ref "R10") (pin "2") (pinfunction "2_2") (pintype "passive"))
      (node (ref "SW4") (pin "2") (pinfunction "2_2") (pintype "passive"))
      (node (ref "SW4") (pin "3") (pinfunction "1_3") (pintype "passive"))
      (node (ref "U9") (pin "20") (pinfunction "PB2/BOOT1_20") (pintype "bidirectional"))
    )
    (net (code "67") (name "/BUTTON_LED") (class "Default")
      (node (ref "P6") (pin "1") (pinfunction "1_1") (pintype "passive"))
      (node (ref "R8") (pin "2") (pinfunction "2_2") (pintype "passive"))
      (node (ref "SW2") (pin "2") (pinfunction "2_2") (pintype "passive"))
      (node (ref "SW2") (pin "3") (pinfunction "1_3") (pintype "passive"))
      (node (ref "U9") (pin "18") (pinfunction "PB0/ADC12_IN8/TIM3_CH3_¦_TIM1_CH2N_18") (pintype "bidirectional"))
    )
    (net (code "68") (name "/BUTTON_MODE") (class "Default")
      (node (ref "P7") (pin "1") (pinfunction "1_1") (pintype "passive"))
      (node (ref "R9") (pin "2") (pinfunction "2_2") (pintype "passive"))
      (node (ref "SW3") (pin "2") (pinfunction "2_2") (pintype "passive"))
      (node (ref "SW3") (pin "3") (pinfunction "1_3") (pintype "passive"))
      (node (ref "U9") (pin "19") (pinfunction "PB1/ADC12_IN9/TIM3_CH4_¦_TIM1_CH3N_19") (pintype "bidirectional"))
    )
    (net (code "69") (name "/BUZZER(TIM)") (class "Default")
      (node (ref "R38") (pin "2") (pinfunction "2_2") (pintype "passive"))
      (node (ref "U9") (pin "11") (pinfunction "PA1/USART2_RTS/ADC12_IN1/TIM2_CH2_11") (pintype "bidirectional"))
    )
    (net (code "70") (name "/DEBUG_LED") (class "Default")
      (node (ref "LED5") (pin "2") (pinfunction "K_2") (pintype "passive"))
      (node (ref "U9") (pin "25") (pinfunction "PB12/SPI2_NSS/I2C2_SMBAl/USART3_CK/TIM1_BKIN_25") (pintype "bidirectional"))
    )
    (net (code "71") (name "/I2C1_SCL") (class "Default")
      (node (ref "R4") (pin "1") (pinfunction "1_1") (pintype "passive"))
      (node (ref "U3") (pin "16") (pinfunction "SCL_16") (pintype "passive"))
      (node (ref "U9") (pin "42") (pinfunction "PB6/I2C1_SCL/TIM4_CH1_¦_USART1_TX_42") (pintype "bidirectional"))
    )
    (net (code "72") (name "/I2C1_SDA") (class "Default")
      (node (ref "R5") (pin "1") (pinfunction "1_1") (pintype "passive"))
      (node (ref "U3") (pin "15") (pinfunction "SDA_15") (pintype "passive"))
      (node (ref "U9") (pin "43") (pinfunction "PB7/I2C1_SDA/TIM4_CH2_¦_USART1_RX_43") (pintype "bidirectional"))
    )
    (net (code "73") (name "/I2C2_SCL") (class "Default")
      (node (ref "P4") (pin "3") (pinfunction "3_3") (pintype "passive"))
      (node (ref "U9") (pin "21") (pinfunction "PB10/I2C2_SCL/USART3_TX_¦_TIM2_CH3_21") (pintype "bidirectional"))
    )
    (net (code "74") (name "/I2C2_SDA") (class "Default")
      (node (ref "P4") (pin "4") (pinfunction "4_4") (pintype "passive"))
      (node (ref "U9") (pin "22") (pinfunction "PB11/I2C2_SDA/USART3_RX_¦_TIM2_CH4_22") (pintype "bidirectional"))
    )
    (net (code "75") (name "/OUTPUT 1HZ") (class "Default")
      (node (ref "R1") (pin "1") (pinfunction "1_1") (pintype "passive"))
      (node (ref "R2") (pin "1") (pinfunction "1_1") (pintype "passive"))
      (node (ref "R83") (pin "1") (pinfunction "1_1") (pintype "passive"))
    )
    (net (code "76") (name "/OUTPUT 1HZ DS") (class "Default")
      (node (ref "R1") (pin "2") (pinfunction "2_2") (pintype "passive"))
      (node (ref "R6") (pin "1") (pinfunction "1_1") (pintype "passive"))
      (node (ref "U3") (pin "3") (pinfunction "~{INT}/SQW_3") (pintype "passive"))
    )
    (net (code "77") (name "/OUTPUT 1HZ MCU") (class "Default")
      (node (ref "R2") (pin "2") (pinfunction "2_2") (pintype "passive"))
      (node (ref "U9") (pin "26") (pinfunction "PB13/SPI2_SCK/USART3_CTS/TIM1_CH1N_26") (pintype "bidirectional"))
    )
    (net (code "78") (name "/SET HC12") (class "Default")
      (node (ref "R7") (pin "2") (pinfunction "2_2") (pintype "passive"))
      (node (ref "U9") (pin "10") (pinfunction "PA0/WKUP/USART2_CTS/ADC12_IN0/TIM2_CH1_ETR_10") (pintype "bidirectional"))
    )
    (net (code "79") (name "/SPI 1_2") (class "Default")
      (node (ref "U13") (pin "9") (pinfunction "SDO_9") (pintype "passive"))
      (node (ref "U17") (pin "14") (pinfunction "SDI_14") (pintype "passive"))
    )
    (net (code "80") (name "/SPI 1_3") (class "Default")
      (node (ref "U17") (pin "9") (pinfunction "SDO_9") (pintype "passive"))
      (node (ref "U18") (pin "14") (pinfunction "SDI_14") (pintype "passive"))
    )
    (net (code "81") (name "/SPI DATA") (class "Default")
      (node (ref "U12") (pin "14") (pinfunction "SDI_14") (pintype "passive"))
      (node (ref "U9") (pin "17") (pinfunction "PA7/SPI1_MOSI/ADC12_IN7/TIM3_CH2_¦_TIM1_CH1N_17") (pintype "bidirectional"))
    )
    (net (code "82") (name "/SPI_CLK") (class "Default")
      (node (ref "U12") (pin "11") (pinfunction "SH_CP_11") (pintype "passive"))
      (node (ref "U13") (pin "11") (pinfunction "SH_CP_11") (pintype "passive"))
      (node (ref "U17") (pin "11") (pinfunction "SH_CP_11") (pintype "passive"))
      (node (ref "U18") (pin "11") (pinfunction "SH_CP_11") (pintype "passive"))
      (node (ref "U9") (pin "16") (pinfunction "PA6/SPI1_MISO/ADC12_IN6/TIM3_CH1_¦_TIM1_BKIN_16") (pintype "bidirectional"))
    )
    (net (code "83") (name "/SPI_LAT") (class "Default")
      (node (ref "U12") (pin "12") (pinfunction "ST_CP_12") (pintype "passive"))
      (node (ref "U13") (pin "12") (pinfunction "ST_CP_12") (pintype "passive"))
      (node (ref "U17") (pin "12") (pinfunction "ST_CP_12") (pintype "passive"))
      (node (ref "U18") (pin "12") (pinfunction "ST_CP_12") (pintype "passive"))
      (node (ref "U9") (pin "15") (pinfunction "PA5/SPI1_SCK/ADC12_IN5_15") (pintype "bidirectional"))
    )
    (net (code "84") (name "/SWCLK") (class "Default")
      (node (ref "P2") (pin "1") (pinfunction "1_1") (pintype "passive"))
      (node (ref "U9") (pin "37") (pinfunction "JTCK/SWCLK_¦_PA14_37") (pintype "bidirectional"))
    )
    (net (code "85") (name "/SWDIO") (class "Default")
      (node (ref "P2") (pin "2") (pinfunction "2_2") (pintype "passive"))
      (node (ref "U9") (pin "34") (pinfunction "JTMS/SWDIO_¦_PA13_34") (pintype "bidirectional"))
    )
    (net (code "86") (name "/USART1_RX") (class "Default")
      (node (ref "P1") (pin "1") (pinfunction "1_1") (pintype "passive"))
      (node (ref "U9") (pin "31") (pinfunction "PA10/USART1_RX/TIM1_CH3_31") (pintype "bidirectional"))
    )
    (net (code "87") (name "/USART1_TX") (class "Default")
      (node (ref "P1") (pin "2") (pinfunction "2_2") (pintype "passive"))
      (node (ref "U9") (pin "30") (pinfunction "PA9/USART1_TX/TM1_CH2_30") (pintype "bidirectional"))
    )
    (net (code "88") (name "/USART2_RX") (class "Default")
      (node (ref "R71") (pin "1") (pinfunction "1_1") (pintype "passive"))
      (node (ref "U9") (pin "13") (pinfunction "PA3/USART2_RX/ADC12_IN3/TIM2_CH4_13") (pintype "bidirectional"))
    )
    (net (code "89") (name "/USART2_TX") (class "Default")
      (node (ref "R66") (pin "1") (pinfunction "1_1") (pintype "passive"))
      (node (ref "U9") (pin "12") (pinfunction "PA2/USART2_TX/ADC12_IN2/TIM2_CH3_12") (pintype "bidirectional"))
    )
    (net (code "90") (name "/VLED7") (class "Default")
      (node (ref "D10") (pin "1") (pinfunction "AT_1") (pintype "passive"))
      (node (ref "D10") (pin "8") (pinfunction "AL_8") (pintype "passive"))
      (node (ref "D11") (pin "1") (pinfunction "AT_1") (pintype "passive"))
      (node (ref "D11") (pin "8") (pinfunction "AL_8") (pintype "passive"))
      (node (ref "D12") (pin "1") (pinfunction "AT_1") (pintype "passive"))
      (node (ref "D12") (pin "8") (pinfunction "AL_8") (pintype "passive"))
      (node (ref "D13") (pin "1") (pinfunction "AT_1") (pintype "passive"))
      (node (ref "D13") (pin "8") (pinfunction "AL_8") (pintype "passive"))
      (node (ref "L3") (pin "1") (pinfunction "1_1") (pintype "passive"))
      (node (ref "L4") (pin "1") (pinfunction "1_1") (pintype "passive"))
      (node (ref "R12") (pin "1") (pinfunction "1_1") (pintype "passive"))
      (node (ref "R13") (pin "1") (pinfunction "1_1") (pintype "passive"))
      (node (ref "R14") (pin "1") (pinfunction "1_1") (pintype "passive"))
      (node (ref "R15") (pin "1") (pinfunction "1_1") (pintype "passive"))
      (node (ref "U1") (pin "10") (pinfunction "COM_10") (pintype "passive"))
      (node (ref "U2") (pin "10") (pinfunction "COM_10") (pintype "passive"))
      (node (ref "U4") (pin "10") (pinfunction "COM_10") (pintype "passive"))
      (node (ref "U5") (pin "10") (pinfunction "COM_10") (pintype "passive"))
    )
    (net (code "91") (name "3V3") (class "Default")
      (node (ref "C13") (pin "1") (pinfunction "1_1") (pintype "passive"))
      (node (ref "C14") (pin "1") (pinfunction "1_1") (pintype "passive"))
      (node (ref "C22") (pin "1") (pinfunction "1_1") (pintype "passive"))
      (node (ref "C23") (pin "1") (pinfunction "1_1") (pintype "passive"))
      (node (ref "C24") (pin "1") (pinfunction "1_1") (pintype "passive"))
      (node (ref "C25") (pin "1") (pinfunction "1_1") (pintype "passive"))
      (node (ref "D8") (pin "2") (pinfunction "K_2") (pintype "passive"))
      (node (ref "L2") (pin "2") (pinfunction "2_2") (pintype "passive"))
      (node (ref "P4") (pin "1") (pinfunction "1_1") (pintype "passive"))
      (node (ref "R10") (pin "1") (pinfunction "1_1") (pintype "passive"))
      (node (ref "R11") (pin "1") (pinfunction "1_1") (pintype "passive"))
      (node (ref "R16") (pin "2") (pinfunction "2_2") (pintype "passive"))
      (node (ref "R41") (pin "2") (pinfunction "2_2") (pintype "passive"))
      (node (ref "R44") (pin "2") (pinfunction "2_2") (pintype "passive"))
      (node (ref "R8") (pin "1") (pinfunction "1_1") (pintype "passive"))
      (node (ref "R9") (pin "1") (pinfunction "1_1") (pintype "passive"))
      (node (ref "U11") (pin "2") (pinfunction "VOUT_2") (pintype "passive"))
      (node (ref "U11") (pin "4") (pinfunction "VO_4") (pintype "passive"))
      (node (ref "U12") (pin "10") (pinfunction "~{CLR}_10") (pintype "passive"))
      (node (ref "U12") (pin "16") (pinfunction "VCC_16") (pintype "passive"))
      (node (ref "U13") (pin "10") (pinfunction "~{CLR}_10") (pintype "passive"))
      (node (ref "U13") (pin "16") (pinfunction "VCC_16") (pintype "passive"))
      (node (ref "U17") (pin "10") (pinfunction "~{CLR}_10") (pintype "passive"))
      (node (ref "U17") (pin "16") (pinfunction "VCC_16") (pintype "passive"))
      (node (ref "U18") (pin "10") (pinfunction "~{CLR}_10") (pintype "passive"))
      (node (ref "U18") (pin "16") (pinfunction "VCC_16") (pintype "passive"))
    )
    (net (code "92") (name "GND") (class "Default")
      (node (ref "C1") (pin "2") (pinfunction "2_2") (pintype "passive"))
      (node (ref "C10") (pin "2") (pinfunction "2_2") (pintype "passive"))
      (node (ref "C12") (pin "2") (pinfunction "2_2") (pintype "passive"))
      (node (ref "C13") (pin "2") (pinfunction "2_2") (pintype "passive"))
      (node (ref "C14") (pin "2") (pinfunction "2_2") (pintype "passive"))
      (node (ref "C16") (pin "2") (pinfunction "2_2") (pintype "passive"))
      (node (ref "C17") (pin "2") (pinfunction "2_2") (pintype "passive"))
      (node (ref "C18") (pin "2") (pinfunction "2_2") (pintype "passive"))
      (node (ref "C19") (pin "2") (pinfunction "2_2") (pintype "passive"))
      (node (ref "C2") (pin "2") (pinfunction "2_2") (pintype "passive"))
      (node (ref "C20") (pin "2") (pinfunction "2_2") (pintype "passive"))
      (node (ref "C22") (pin "2") (pinfunction "2_2") (pintype "passive"))
      (node (ref "C23") (pin "2") (pinfunction "2_2") (pintype "passive"))
      (node (ref "C24") (pin "2") (pinfunction "2_2") (pintype "passive"))
      (node (ref "C25") (pin "2") (pinfunction "2_2") (pintype "passive"))
      (node (ref "C5") (pin "2") (pinfunction "2_2") (pintype "passive"))
      (node (ref "C6") (pin "2") (pinfunction "2_2") (pintype "passive"))
      (node (ref "C7") (pin "2") (pinfunction "2_2") (pintype "passive"))
      (node (ref "C8") (pin "2") (pinfunction "2_2") (pintype "passive"))
      (node (ref "C9") (pin "2") (pinfunction "2_2") (pintype "passive"))
      (node (ref "CR1") (pin "2") (pinfunction "GND_2") (pintype "passive"))
      (node (ref "D6") (pin "1") (pinfunction "A_1") (pintype "passive"))
      (node (ref "D8") (pin "1") (pinfunction "A_1") (pintype "passive"))
      (node (ref "HC1") (pin "2") (pinfunction "GND_2") (pintype "passive"))
      (node (ref "JP1") (pin "2") (pinfunction "2_2") (pintype "passive"))
      (node (ref "LED3") (pin "2") (pinfunction "K_2") (pintype "passive"))
      (node (ref "LED4") (pin "2") (pinfunction "K_2") (pintype "passive"))
      (node (ref "P1") (pin "3") (pinfunction "3_3") (pintype "passive"))
      (node (ref "P2") (pin "3") (pinfunction "3_3") (pintype "passive"))
      (node (ref "P4") (pin "2") (pinfunction "2_2") (pintype "passive"))
      (node (ref "P5") (pin "1") (pinfunction "1_1") (pintype "passive"))
      (node (ref "P6") (pin "2") (pinfunction "2_2") (pintype "passive"))
      (node (ref "P7") (pin "2") (pinfunction "2_2") (pintype "passive"))
      (node (ref "P8") (pin "2") (pinfunction "2_2") (pintype "passive"))
      (node (ref "P9") (pin "2") (pinfunction "2_2") (pintype "passive"))
      (node (ref "Q2") (pin "2") (pinfunction "E_2") (pintype "passive"))
      (node (ref "Q4") (pin "1") (pinfunction "E_1") (pintype "passive"))
      (node (ref "R39") (pin "2") (pinfunction "2_2") (pintype "passive"))
      (node (ref "R43") (pin "1") (pinfunction "1_1") (pintype "passive"))
      (node (ref "R84") (pin "2") (pinfunction "2_2") (pintype "passive"))
      (node (ref "SW1") (pin "1") (pinfunction "1_1") (pintype "passive"))
      (node (ref "SW2") (pin "1") (pinfunction "1_1") (pintype "passive"))
      (node (ref "SW2") (pin "4") (pinfunction "2_4") (pintype "passive"))
      (node (ref "SW3") (pin "1") (pinfunction "1_1") (pintype "passive"))
      (node (ref "SW3") (pin "4") (pinfunction "2_4") (pintype "passive"))
      (node (ref "SW4") (pin "1") (pinfunction "1_1") (pintype "passive"))
      (node (ref "SW4") (pin "4") (pinfunction "2_4") (pintype "passive"))
      (node (ref "SW5") (pin "1") (pinfunction "1_1") (pintype "passive"))
      (node (ref "SW5") (pin "4") (pinfunction "2_4") (pintype "passive"))
      (node (ref "U1") (pin "9") (pinfunction "GND_9") (pintype "passive"))
      (node (ref "U10") (pin "3") (pinfunction "GND_3") (pintype "passive"))
      (node (ref "U10") (pin "5") (pinfunction "~{ON}/OFF_5") (pintype "passive"))
      (node (ref "U10") (pin "6") (pinfunction "PAD_6") (pintype "passive"))
      (node (ref "U11") (pin "1") (pinfunction "GND_1") (pintype "passive"))
      (node (ref "U12") (pin "13") (pinfunction "~{OE}_13") (pintype "passive"))
      (node (ref "U12") (pin "8") (pinfunction "GND_8") (pintype "passive"))
      (node (ref "U13") (pin "13") (pinfunction "~{OE}_13") (pintype "passive"))
      (node (ref "U13") (pin "8") (pinfunction "GND_8") (pintype "passive"))
      (node (ref "U17") (pin "13") (pinfunction "~{OE}_13") (pintype "passive"))
      (node (ref "U17") (pin "8") (pinfunction "GND_8") (pintype "passive"))
      (node (ref "U18") (pin "13") (pinfunction "~{OE}_13") (pintype "passive"))
      (node (ref "U18") (pin "8") (pinfunction "GND_8") (pintype "passive"))
      (node (ref "U2") (pin "9") (pinfunction "GND_9") (pintype "passive"))
      (node (ref "U3") (pin "10") (pinfunction "NC_10") (pintype "passive"))
      (node (ref "U3") (pin "11") (pinfunction "NC_11") (pintype "passive"))
      (node (ref "U3") (pin "12") (pinfunction "NC_12") (pintype "passive"))
      (node (ref "U3") (pin "13") (pinfunction "GND_13") (pintype "passive"))
      (node (ref "U3") (pin "5") (pinfunction "NC_5") (pintype "passive"))
      (node (ref "U3") (pin "6") (pinfunction "NC_6") (pintype "passive"))
      (node (ref "U3") (pin "7") (pinfunction "NC_7") (pintype "passive"))
      (node (ref "U3") (pin "8") (pinfunction "NC_8") (pintype "passive"))
      (node (ref "U3") (pin "9") (pinfunction "NC_9") (pintype "passive"))
      (node (ref "U4") (pin "9") (pinfunction "GND_9") (pintype "passive"))
      (node (ref "U5") (pin "9") (pinfunction "GND_9") (pintype "passive"))
      (node (ref "U9") (pin "23") (pinfunction "VSS_1_23") (pintype "power_in"))
      (node (ref "U9") (pin "35") (pinfunction "VSS_2_35") (pintype "power_in"))
      (node (ref "U9") (pin "47") (pinfunction "VSS_3_47") (pintype "power_in"))
      (node (ref "U9") (pin "8") (pinfunction "VSSA_8") (pintype "power_in"))
    )
    (net (code "93") (name "Net-(C10-Pad1)") (class "Default")
      (node (ref "C10") (pin "1") (pinfunction "1_1") (pintype "passive"))
      (node (ref "R40") (pin "2") (pinfunction "2_2") (pintype "passive"))
      (node (ref "Y1") (pin "1") (pinfunction "1_1") (pintype "passive"))
    )
    (net (code "94") (name "Net-(D5-A)") (class "Default")
      (node (ref "D5") (pin "1") (pinfunction "A_1") (pintype "passive"))
      (node (ref "P5") (pin "2") (pinfunction "2_2") (pintype "passive"))
    )
    (net (code "95") (name "Net-(D6-K)") (class "Default")
      (node (ref "D6") (pin "2") (pinfunction "K_2") (pintype "passive"))
      (node (ref "L1") (pin "1") (pinfunction "1_1") (pintype "passive"))
      (node (ref "U10") (pin "2") (pinfunction "OUT_2") (pintype "passive"))
    )
    (net (code "96") (name "Net-(D7-K)") (class "Default")
      (node (ref "C12") (pin "1") (pinfunction "1_1") (pintype "passive"))
      (node (ref "D7") (pin "2") (pinfunction "K_2") (pintype "passive"))
      (node (ref "U11") (pin "3") (pinfunction "VIN_3") (pintype "power_in"))
    )
    (net (code "97") (name "Net-(HC1-RXD)") (class "Default")
      (node (ref "HC1") (pin "3") (pinfunction "RXD_3") (pintype "passive"))
      (node (ref "R66") (pin "2") (pinfunction "2_2") (pintype "passive"))
    )
    (net (code "98") (name "Net-(HC1-SET)") (class "Default")
      (node (ref "HC1") (pin "5") (pinfunction "SET_5") (pintype "passive"))
      (node (ref "R7") (pin "1") (pinfunction "1_1") (pintype "passive"))
    )
    (net (code "99") (name "Net-(HC1-TXD)") (class "Default")
      (node (ref "HC1") (pin "4") (pinfunction "TXD_4") (pintype "passive"))
      (node (ref "R71") (pin "2") (pinfunction "2_2") (pintype "passive"))
    )
    (net (code "100") (name "Net-(LED3-A)") (class "Default")
      (node (ref "LED3") (pin "1") (pinfunction "A_1") (pintype "passive"))
      (node (ref "R36") (pin "1") (pinfunction "1_1") (pintype "passive"))
    )
    (net (code "101") (name "Net-(LED4-A)") (class "Default")
      (node (ref "LED4") (pin "1") (pinfunction "A_1") (pintype "passive"))
      (node (ref "R41") (pin "1") (pinfunction "1_1") (pintype "passive"))
    )
    (net (code "102") (name "Net-(LED5-A)") (class "Default")
      (node (ref "LED5") (pin "1") (pinfunction "A_1") (pintype "passive"))
      (node (ref "R44") (pin "1") (pinfunction "1_1") (pintype "passive"))
    )
    (net (code "103") (name "Net-(LED7-A)") (class "Default")
      (node (ref "LED7") (pin "1") (pinfunction "A_1") (pintype "passive"))
      (node (ref "LED8") (pin "1") (pinfunction "A_1") (pintype "passive"))
      (node (ref "R82") (pin "1") (pinfunction "1_1") (pintype "passive"))
    )
    (net (code "104") (name "Net-(LED7-K)") (class "Default")
      (node (ref "LED7") (pin "2") (pinfunction "K_2") (pintype "passive"))
      (node (ref "LED8") (pin "2") (pinfunction "K_2") (pintype "passive"))
      (node (ref "Q4") (pin "2") (pinfunction "C_2") (pintype "passive"))
    )
    (net (code "105") (name "Net-(P3-Pad2)") (class "Default")
      (node (ref "P3") (pin "2") (pinfunction "2_2") (pintype "passive"))
      (node (ref "R37") (pin "2") (pinfunction "2_2") (pintype "passive"))
    )
    (net (code "106") (name "Net-(Q2-B)") (class "Default")
      (node (ref "Q2") (pin "1") (pinfunction "B_1") (pintype "passive"))
      (node (ref "R38") (pin "1") (pinfunction "1_1") (pintype "passive"))
      (node (ref "R39") (pin "1") (pinfunction "1_1") (pintype "passive"))
    )
    (net (code "107") (name "Net-(Q2-C)") (class "Default")
      (node (ref "Q2") (pin "3") (pinfunction "C_3") (pintype "passive"))
      (node (ref "R37") (pin "1") (pinfunction "1_1") (pintype "passive"))
    )
    (net (code "108") (name "Net-(Q4-B)") (class "Default")
      (node (ref "Q4") (pin "3") (pinfunction "B_3") (pintype "passive"))
      (node (ref "R83") (pin "2") (pinfunction "2_2") (pintype "passive"))
      (node (ref "R84") (pin "1") (pinfunction "1_1") (pintype "passive"))
    )
    (net (code "109") (name "Net-(U1-O1)") (class "Default")
      (node (ref "R12") (pin "2") (pinfunction "2_2") (pintype "passive"))
      (node (ref "R45") (pin "1") (pinfunction "1_1") (pintype "passive"))
      (node (ref "U1") (pin "18") (pinfunction "O1_18") (pintype "passive"))
    )
    (net (code "110") (name "Net-(U1-O2)") (class "Default")
      (node (ref "R12") (pin "3") (pinfunction "3_3") (pintype "passive"))
      (node (ref "R47") (pin "1") (pinfunction "1_1") (pintype "passive"))
      (node (ref "U1") (pin "17") (pinfunction "O2_17") (pintype "passive"))
    )
    (net (code "111") (name "Net-(U1-O3)") (class "Default")
      (node (ref "R12") (pin "4") (pinfunction "4_4") (pintype "passive"))
      (node (ref "R49") (pin "1") (pinfunction "1_1") (pintype "passive"))
      (node (ref "U1") (pin "16") (pinfunction "O3_16") (pintype "passive"))
    )
    (net (code "112") (name "Net-(U1-O4)") (class "Default")
      (node (ref "R12") (pin "5") (pinfunction "5_5") (pintype "passive"))
      (node (ref "R52") (pin "1") (pinfunction "1_1") (pintype "passive"))
      (node (ref "U1") (pin "15") (pinfunction "O4_15") (pintype "passive"))
    )
    (net (code "113") (name "Net-(U1-O5)") (class "Default")
      (node (ref "R12") (pin "6") (pinfunction "6_6") (pintype "passive"))
      (node (ref "R54") (pin "1") (pinfunction "1_1") (pintype "passive"))
      (node (ref "U1") (pin "14") (pinfunction "O5_14") (pintype "passive"))
    )
    (net (code "114") (name "Net-(U1-O6)") (class "Default")
      (node (ref "R12") (pin "7") (pinfunction "7_7") (pintype "passive"))
      (node (ref "R56") (pin "1") (pinfunction "1_1") (pintype "passive"))
      (node (ref "U1") (pin "13") (pinfunction "O6_13") (pintype "passive"))
    )
    (net (code "115") (name "Net-(U1-O7)") (class "Default")
      (node (ref "R12") (pin "8") (pinfunction "8_8") (pintype "passive"))
      (node (ref "R58") (pin "1") (pinfunction "1_1") (pintype "passive"))
      (node (ref "U1") (pin "12") (pinfunction "O7_12") (pintype "passive"))
    )
    (net (code "116") (name "Net-(U1-O8)") (class "Default")
      (node (ref "R12") (pin "9") (pinfunction "9_9") (pintype "passive"))
      (node (ref "R60") (pin "1") (pinfunction "1_1") (pintype "passive"))
      (node (ref "U1") (pin "11") (pinfunction "O8_11") (pintype "passive"))
    )
    (net (code "117") (name "Net-(U2-O1)") (class "Default")
      (node (ref "R13") (pin "2") (pinfunction "2_2") (pintype "passive"))
      (node (ref "R46") (pin "1") (pinfunction "1_1") (pintype "passive"))
      (node (ref "U2") (pin "18") (pinfunction "O1_18") (pintype "passive"))
    )
    (net (code "118") (name "Net-(U2-O2)") (class "Default")
      (node (ref "R13") (pin "3") (pinfunction "3_3") (pintype "passive"))
      (node (ref "R48") (pin "1") (pinfunction "1_1") (pintype "passive"))
      (node (ref "U2") (pin "17") (pinfunction "O2_17") (pintype "passive"))
    )
    (net (code "119") (name "Net-(U2-O3)") (class "Default")
      (node (ref "R13") (pin "4") (pinfunction "4_4") (pintype "passive"))
      (node (ref "R50") (pin "1") (pinfunction "1_1") (pintype "passive"))
      (node (ref "U2") (pin "16") (pinfunction "O3_16") (pintype "passive"))
    )
    (net (code "120") (name "Net-(U2-O4)") (class "Default")
      (node (ref "R13") (pin "5") (pinfunction "5_5") (pintype "passive"))
      (node (ref "R53") (pin "1") (pinfunction "1_1") (pintype "passive"))
      (node (ref "U2") (pin "15") (pinfunction "O4_15") (pintype "passive"))
    )
    (net (code "121") (name "Net-(U2-O5)") (class "Default")
      (node (ref "R13") (pin "6") (pinfunction "6_6") (pintype "passive"))
      (node (ref "R55") (pin "1") (pinfunction "1_1") (pintype "passive"))
      (node (ref "U2") (pin "14") (pinfunction "O5_14") (pintype "passive"))
    )
    (net (code "122") (name "Net-(U2-O6)") (class "Default")
      (node (ref "R13") (pin "7") (pinfunction "7_7") (pintype "passive"))
      (node (ref "R57") (pin "1") (pinfunction "1_1") (pintype "passive"))
      (node (ref "U2") (pin "13") (pinfunction "O6_13") (pintype "passive"))
    )
    (net (code "123") (name "Net-(U2-O7)") (class "Default")
      (node (ref "R13") (pin "8") (pinfunction "8_8") (pintype "passive"))
      (node (ref "R59") (pin "1") (pinfunction "1_1") (pintype "passive"))
      (node (ref "U2") (pin "12") (pinfunction "O7_12") (pintype "passive"))
    )
    (net (code "124") (name "Net-(U2-O8)") (class "Default")
      (node (ref "R13") (pin "9") (pinfunction "9_9") (pintype "passive"))
      (node (ref "R61") (pin "1") (pinfunction "1_1") (pintype "passive"))
      (node (ref "U2") (pin "11") (pinfunction "O8_11") (pintype "passive"))
    )
    (net (code "125") (name "Net-(U3-32KHz)") (class "Default")
      (node (ref "R3") (pin "2") (pinfunction "2_2") (pintype "passive"))
      (node (ref "U3") (pin "1") (pinfunction "32KHz_1") (pintype "passive"))
    )
    (net (code "126") (name "Net-(U4-O1)") (class "Default")
      (node (ref "R14") (pin "2") (pinfunction "2_2") (pintype "passive"))
      (node (ref "R64") (pin "1") (pinfunction "1_1") (pintype "passive"))
      (node (ref "U4") (pin "18") (pinfunction "O1_18") (pintype "passive"))
    )
    (net (code "127") (name "Net-(U4-O2)") (class "Default")
      (node (ref "R14") (pin "3") (pinfunction "3_3") (pintype "passive"))
      (node (ref "R67") (pin "1") (pinfunction "1_1") (pintype "passive"))
      (node (ref "U4") (pin "17") (pinfunction "O2_17") (pintype "passive"))
    )
    (net (code "128") (name "Net-(U4-O3)") (class "Default")
      (node (ref "R14") (pin "4") (pinfunction "4_4") (pintype "passive"))
      (node (ref "R69") (pin "1") (pinfunction "1_1") (pintype "passive"))
      (node (ref "U4") (pin "16") (pinfunction "O3_16") (pintype "passive"))
    )
    (net (code "129") (name "Net-(U4-O4)") (class "Default")
      (node (ref "R14") (pin "5") (pinfunction "5_5") (pintype "passive"))
      (node (ref "R72") (pin "1") (pinfunction "1_1") (pintype "passive"))
      (node (ref "U4") (pin "15") (pinfunction "O4_15") (pintype "passive"))
    )
    (net (code "130") (name "Net-(U4-O5)") (class "Default")
      (node (ref "R14") (pin "6") (pinfunction "6_6") (pintype "passive"))
      (node (ref "R74") (pin "1") (pinfunction "1_1") (pintype "passive"))
      (node (ref "U4") (pin "14") (pinfunction "O5_14") (pintype "passive"))
    )
    (net (code "131") (name "Net-(U4-O6)") (class "Default")
      (node (ref "R14") (pin "7") (pinfunction "7_7") (pintype "passive"))
      (node (ref "R76") (pin "1") (pinfunction "1_1") (pintype "passive"))
      (node (ref "U4") (pin "13") (pinfunction "O6_13") (pintype "passive"))
    )
    (net (code "132") (name "Net-(U4-O7)") (class "Default")
      (node (ref "R14") (pin "8") (pinfunction "8_8") (pintype "passive"))
      (node (ref "R78") (pin "1") (pinfunction "1_1") (pintype "passive"))
      (node (ref "U4") (pin "12") (pinfunction "O7_12") (pintype "passive"))
    )
    (net (code "133") (name "Net-(U4-O8)") (class "Default")
      (node (ref "R14") (pin "9") (pinfunction "9_9") (pintype "passive"))
      (node (ref "R80") (pin "1") (pinfunction "1_1") (pintype "passive"))
      (node (ref "U4") (pin "11") (pinfunction "O8_11") (pintype "passive"))
    )
    (net (code "134") (name "Net-(U5-O1)") (class "Default")
      (node (ref "R15") (pin "2") (pinfunction "2_2") (pintype "passive"))
      (node (ref "R65") (pin "1") (pinfunction "1_1") (pintype "passive"))
      (node (ref "U5") (pin "18") (pinfunction "O1_18") (pintype "passive"))
    )
    (net (code "135") (name "Net-(U5-O2)") (class "Default")
      (node (ref "R15") (pin "3") (pinfunction "3_3") (pintype "passive"))
      (node (ref "R68") (pin "1") (pinfunction "1_1") (pintype "passive"))
      (node (ref "U5") (pin "17") (pinfunction "O2_17") (pintype "passive"))
    )
    (net (code "136") (name "Net-(U5-O3)") (class "Default")
      (node (ref "R15") (pin "4") (pinfunction "4_4") (pintype "passive"))
      (node (ref "R70") (pin "1") (pinfunction "1_1") (pintype "passive"))
      (node (ref "U5") (pin "16") (pinfunction "O3_16") (pintype "passive"))
    )
    (net (code "137") (name "Net-(U5-O4)") (class "Default")
      (node (ref "R15") (pin "5") (pinfunction "5_5") (pintype "passive"))
      (node (ref "R73") (pin "1") (pinfunction "1_1") (pintype "passive"))
      (node (ref "U5") (pin "15") (pinfunction "O4_15") (pintype "passive"))
    )
    (net (code "138") (name "Net-(U5-O5)") (class "Default")
      (node (ref "R15") (pin "6") (pinfunction "6_6") (pintype "passive"))
      (node (ref "R75") (pin "1") (pinfunction "1_1") (pintype "passive"))
      (node (ref "U5") (pin "14") (pinfunction "O5_14") (pintype "passive"))
    )
    (net (code "139") (name "Net-(U5-O6)") (class "Default")
      (node (ref "R15") (pin "7") (pinfunction "7_7") (pintype "passive"))
      (node (ref "R77") (pin "1") (pinfunction "1_1") (pintype "passive"))
      (node (ref "U5") (pin "13") (pinfunction "O6_13") (pintype "passive"))
    )
    (net (code "140") (name "Net-(U5-O7)") (class "Default")
      (node (ref "R15") (pin "8") (pinfunction "8_8") (pintype "passive"))
      (node (ref "R79") (pin "1") (pinfunction "1_1") (pintype "passive"))
      (node (ref "U5") (pin "12") (pinfunction "O7_12") (pintype "passive"))
    )
    (net (code "141") (name "Net-(U5-O8)") (class "Default")
      (node (ref "R15") (pin "9") (pinfunction "9_9") (pintype "passive"))
      (node (ref "R81") (pin "1") (pinfunction "1_1") (pintype "passive"))
      (node (ref "U5") (pin "11") (pinfunction "O8_11") (pintype "passive"))
    )
    (net (code "142") (name "Net-(U9-BOOT0)") (class "Default")
      (node (ref "R43") (pin "2") (pinfunction "2_2") (pintype "passive"))
      (node (ref "U9") (pin "44") (pinfunction "BOOT0_44") (pintype "input"))
    )
    (net (code "143") (name "Net-(U9-NRST)") (class "Default")
      (node (ref "C16") (pin "1") (pinfunction "1_1") (pintype "passive"))
      (node (ref "SW1") (pin "2") (pinfunction "2_2") (pintype "passive"))
      (node (ref "U9") (pin "7") (pinfunction "NRST_7") (pintype "bidirectional"))
    )
    (net (code "144") (name "Net-(U9-OSC_IN_¦_PD0)") (class "Default")
      (node (ref "C9") (pin "1") (pinfunction "1_1") (pintype "passive"))
      (node (ref "U9") (pin "5") (pinfunction "OSC_IN_¦_PD0_5") (pintype "input"))
      (node (ref "Y1") (pin "2") (pinfunction "2_2") (pintype "passive"))
    )
    (net (code "145") (name "Net-(U9-OSC_OUT_¦_PD1)") (class "Default")
      (node (ref "R40") (pin "1") (pinfunction "1_1") (pintype "passive"))
      (node (ref "U9") (pin "6") (pinfunction "OSC_OUT_¦_PD1_6") (pintype "output"))
    )
    (net (code "146") (name "Net-(U12-SDO)") (class "Default")
      (node (ref "U12") (pin "9") (pinfunction "SDO_9") (pintype "passive"))
      (node (ref "U13") (pin "14") (pinfunction "SDI_14") (pintype "passive"))
    )
    (net (code "147") (name "VBAT") (class "Default")
      (node (ref "C2") (pin "1") (pinfunction "1_1") (pintype "passive"))
      (node (ref "CR1") (pin "1") (pinfunction "VCC_1") (pintype "passive"))
      (node (ref "U3") (pin "14") (pinfunction "VBAT_14") (pintype "passive"))
    )
    (net (code "148") (name "VCC") (class "Default")
      (node (ref "C7") (pin "1") (pinfunction "1_1") (pintype "passive"))
      (node (ref "C8") (pin "1") (pinfunction "1_1") (pintype "passive"))
      (node (ref "D7") (pin "1") (pinfunction "A_1") (pintype "passive"))
      (node (ref "HC1") (pin "1") (pinfunction "VCC_1") (pintype "passive"))
      (node (ref "JP1") (pin "1") (pinfunction "1_1") (pintype "passive"))
      (node (ref "L1") (pin "2") (pinfunction "2_2") (pintype "passive"))
      (node (ref "L4") (pin "2") (pinfunction "2_2") (pintype "passive"))
      (node (ref "P1") (pin "4") (pinfunction "4_4") (pintype "passive"))
      (node (ref "P3") (pin "1") (pinfunction "1_1") (pintype "passive"))
      (node (ref "R17") (pin "2") (pinfunction "2_2") (pintype "passive"))
      (node (ref "R36") (pin "2") (pinfunction "2_2") (pintype "passive"))
      (node (ref "R82") (pin "2") (pinfunction "2_2") (pintype "passive"))
      (node (ref "U10") (pin "4") (pinfunction "FB_4") (pintype "passive"))
    )
    (net (code "149") (name "VDD") (class "Default")
      (node (ref "C17") (pin "1") (pinfunction "1_1") (pintype "passive"))
      (node (ref "C18") (pin "1") (pinfunction "1_1") (pintype "passive"))
      (node (ref "C19") (pin "1") (pinfunction "1_1") (pintype "passive"))
      (node (ref "C20") (pin "1") (pinfunction "1_1") (pintype "passive"))
      (node (ref "L2") (pin "1") (pinfunction "1_1") (pintype "passive"))
      (node (ref "U9") (pin "24") (pinfunction "VDD_1_24") (pintype "power_in"))
      (node (ref "U9") (pin "36") (pinfunction "VDD_2_36") (pintype "power_in"))
      (node (ref "U9") (pin "48") (pinfunction "VDD_3_48") (pintype "power_in"))
      (node (ref "U9") (pin "9") (pinfunction "VDDA_9") (pintype "power_in"))
    )
    (net (code "150") (name "VIN") (class "Default")
      (node (ref "C5") (pin "1") (pinfunction "1_1") (pintype "passive"))
      (node (ref "C6") (pin "1") (pinfunction "1_1") (pintype "passive"))
      (node (ref "D5") (pin "2") (pinfunction "K_2") (pintype "passive"))
      (node (ref "L3") (pin "2") (pinfunction "2_2") (pintype "passive"))
      (node (ref "U10") (pin "1") (pinfunction "VIN_1") (pintype "passive"))
    )
    (net (code "151") (name "VIN_DS") (class "Default")
      (node (ref "C1") (pin "1") (pinfunction "1_1") (pintype "passive"))
      (node (ref "R16") (pin "1") (pinfunction "1_1") (pintype "passive"))
      (node (ref "R17") (pin "1") (pinfunction "1_1") (pintype "passive"))
      (node (ref "R3") (pin "1") (pinfunction "1_1") (pintype "passive"))
      (node (ref "R4") (pin "2") (pinfunction "2_2") (pintype "passive"))
      (node (ref "R5") (pin "2") (pinfunction "2_2") (pintype "passive"))
      (node (ref "R6") (pin "2") (pinfunction "2_2") (pintype "passive"))
      (node (ref "U3") (pin "2") (pinfunction "VCC_2") (pintype "passive"))
    )
    (net (code "152") (name "unconnected-(HC1-ANT-Pad6)") (class "Default")
      (node (ref "HC1") (pin "6") (pinfunction "ANT_6") (pintype "passive+no_connect"))
    )
    (net (code "153") (name "unconnected-(HC1-GND-Pad7)") (class "Default")
      (node (ref "HC1") (pin "7") (pinfunction "GND_7") (pintype "passive+no_connect"))
    )
    (net (code "154") (name "unconnected-(HC1-GND-Pad8)") (class "Default")
      (node (ref "HC1") (pin "8") (pinfunction "GND_8") (pintype "passive+no_connect"))
    )
    (net (code "155") (name "unconnected-(Hole1-Screw-Pad1)") (class "Default")
      (node (ref "Hole1") (pin "1") (pinfunction "Screw_1") (pintype "passive+no_connect"))
    )
    (net (code "156") (name "unconnected-(Hole2-Screw-Pad1)") (class "Default")
      (node (ref "Hole2") (pin "1") (pinfunction "Screw_1") (pintype "passive+no_connect"))
    )
    (net (code "157") (name "unconnected-(Hole3-Screw-Pad1)") (class "Default")
      (node (ref "Hole3") (pin "1") (pinfunction "Screw_1") (pintype "passive+no_connect"))
    )
    (net (code "158") (name "unconnected-(Hole4-Screw-Pad1)") (class "Default")
      (node (ref "Hole4") (pin "1") (pinfunction "Screw_1") (pintype "passive+no_connect"))
    )
    (net (code "159") (name "unconnected-(U3-~{RST}-Pad4)") (class "Default")
      (node (ref "U3") (pin "4") (pinfunction "~{RST}_4") (pintype "passive+no_connect"))
    )
    (net (code "160") (name "unconnected-(U9-JNTRST_¦_TIM3_CH1{slash}PB4{slash}SPI1_MISO-Pad40)") (class "Default")
      (node (ref "U9") (pin "40") (pinfunction "JNTRST_¦_TIM3_CH1/PB4/SPI1_MISO_40") (pintype "bidirectional+no_connect"))
    )
    (net (code "161") (name "unconnected-(U9-JTDI_¦_TIM2_CH1_ETR{slash}PA15{slash}SPI1_NSS-Pad38)") (class "Default")
      (node (ref "U9") (pin "38") (pinfunction "JTDI_¦_TIM2_CH1_ETR/PA15/SPI1_NSS_38") (pintype "bidirectional+no_connect"))
    )
    (net (code "162") (name "unconnected-(U9-JTDO_¦_TIM2_CH2{slash}PB3{slash}TRACESWO{slash}SPI1_SCK-Pad39)") (class "Default")
      (node (ref "U9") (pin "39") (pinfunction "JTDO_¦_TIM2_CH2/PB3/TRACESWO/SPI1_SCK_39") (pintype "bidirectional+no_connect"))
    )
    (net (code "163") (name "unconnected-(U9-PA8{slash}USART1_CK{slash}TIM1_CH1{slash}MCO-Pad29)") (class "Default")
      (node (ref "U9") (pin "29") (pinfunction "PA8/USART1_CK/TIM1_CH1/MCO_29") (pintype "bidirectional+no_connect"))
    )
    (net (code "164") (name "unconnected-(U9-PA11{slash}USART1_CTS{slash}CANRX{slash}USBDM{slash}TIM1_CH4-Pad32)") (class "Default")
      (node (ref "U9") (pin "32") (pinfunction "PA11/USART1_CTS/CANRX/USBDM/TIM1_CH4_32") (pintype "bidirectional+no_connect"))
    )
    (net (code "165") (name "unconnected-(U9-PA12{slash}USART1_RTS{slash}CANTX{slash}USBDP{slash}TIM1_ETR-Pad33)") (class "Default")
      (node (ref "U9") (pin "33") (pinfunction "PA12/USART1_RTS/CANTX/USBDP/TIM1_ETR_33") (pintype "bidirectional+no_connect"))
    )
    (net (code "166") (name "unconnected-(U9-PB5{slash}I2C1_SMBAl_¦_TIM3_CH2{slash}SPI1_MOSI-Pad41)") (class "Default")
      (node (ref "U9") (pin "41") (pinfunction "PB5/I2C1_SMBAl_¦_TIM3_CH2/SPI1_MOSI_41") (pintype "bidirectional+no_connect"))
    )
    (net (code "167") (name "unconnected-(U9-PB8{slash}TIM4_CH3_¦_I2C1_SCL{slash}CANRX-Pad45)") (class "Default")
      (node (ref "U9") (pin "45") (pinfunction "PB8/TIM4_CH3_¦_I2C1_SCL/CANRX_45") (pintype "bidirectional+no_connect"))
    )
    (net (code "168") (name "unconnected-(U9-PB9{slash}TIM4_CH4_¦_I2C1_SDA{slash}CANTX-Pad46)") (class "Default")
      (node (ref "U9") (pin "46") (pinfunction "PB9/TIM4_CH4_¦_I2C1_SDA/CANTX_46") (pintype "bidirectional+no_connect"))
    )
    (net (code "169") (name "unconnected-(U9-PB14{slash}SPI2_MISO{slash}USART3_RTS{slash}TIM1_CH2N-Pad27)") (class "Default")
      (node (ref "U9") (pin "27") (pinfunction "PB14/SPI2_MISO/USART3_RTS/TIM1_CH2N_27") (pintype "bidirectional+no_connect"))
    )
    (net (code "170") (name "unconnected-(U9-PB15{slash}SPI2_MOSI{slash}TIM1_CH3N-Pad28)") (class "Default")
      (node (ref "U9") (pin "28") (pinfunction "PB15/SPI2_MOSI/TIM1_CH3N_28") (pintype "bidirectional+no_connect"))
    )
    (net (code "171") (name "unconnected-(U9-PC13{slash}TAMPER-RTC-Pad2)") (class "Default")
      (node (ref "U9") (pin "2") (pinfunction "PC13/TAMPER-RTC_2") (pintype "bidirectional+no_connect"))
    )
    (net (code "172") (name "unconnected-(U9-PC14{slash}OSC32_IN-Pad3)") (class "Default")
      (node (ref "U9") (pin "3") (pinfunction "PC14/OSC32_IN_3") (pintype "bidirectional+no_connect"))
    )
    (net (code "173") (name "unconnected-(U9-PC15{slash}OSC32_OUT-Pad4)") (class "Default")
      (node (ref "U9") (pin "4") (pinfunction "PC15/OSC32_OUT_4") (pintype "bidirectional+no_connect"))
    )
    (net (code "174") (name "unconnected-(U9-VBAT-Pad1)") (class "Default")
      (node (ref "U9") (pin "1") (pinfunction "VBAT_1") (pintype "power_in+no_connect"))
    )
    (net (code "175") (name "unconnected-(U10-GND-Pad6)") (class "Default")
      (node (ref "U10") (pin "6") (pinfunction "GND_6") (pintype "passive"))
    )
    (net (code "176") (name "unconnected-(U18-SDO-Pad9)") (class "Default")
      (node (ref "U18") (pin "9") (pinfunction "SDO_9") (pintype "passive+no_connect"))
    )
  )
)
